# LCMeter.net
KiCad netlist of a schematic drawn in EAGLE
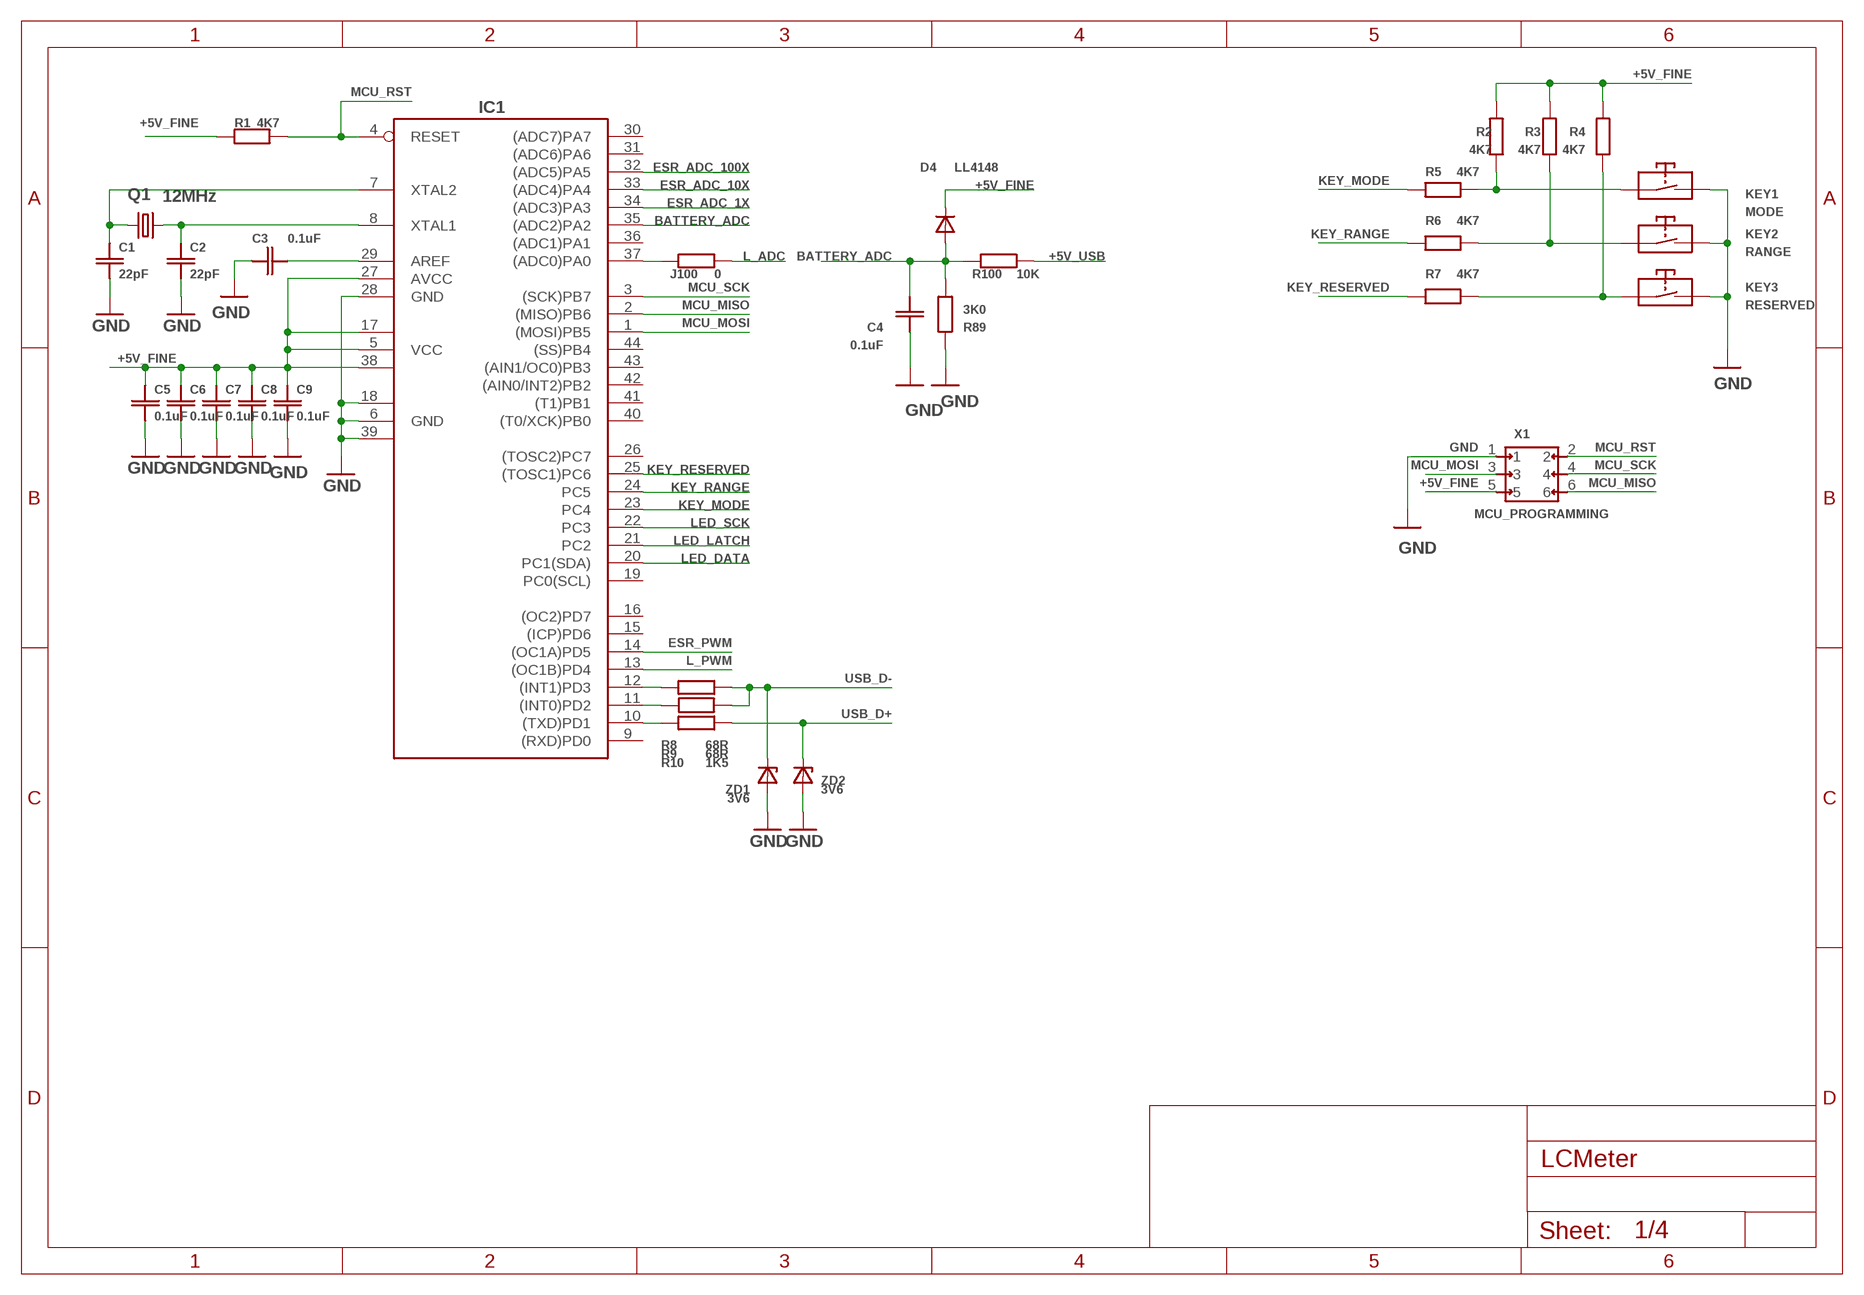
[diagram p0: schematic, sheet 1]
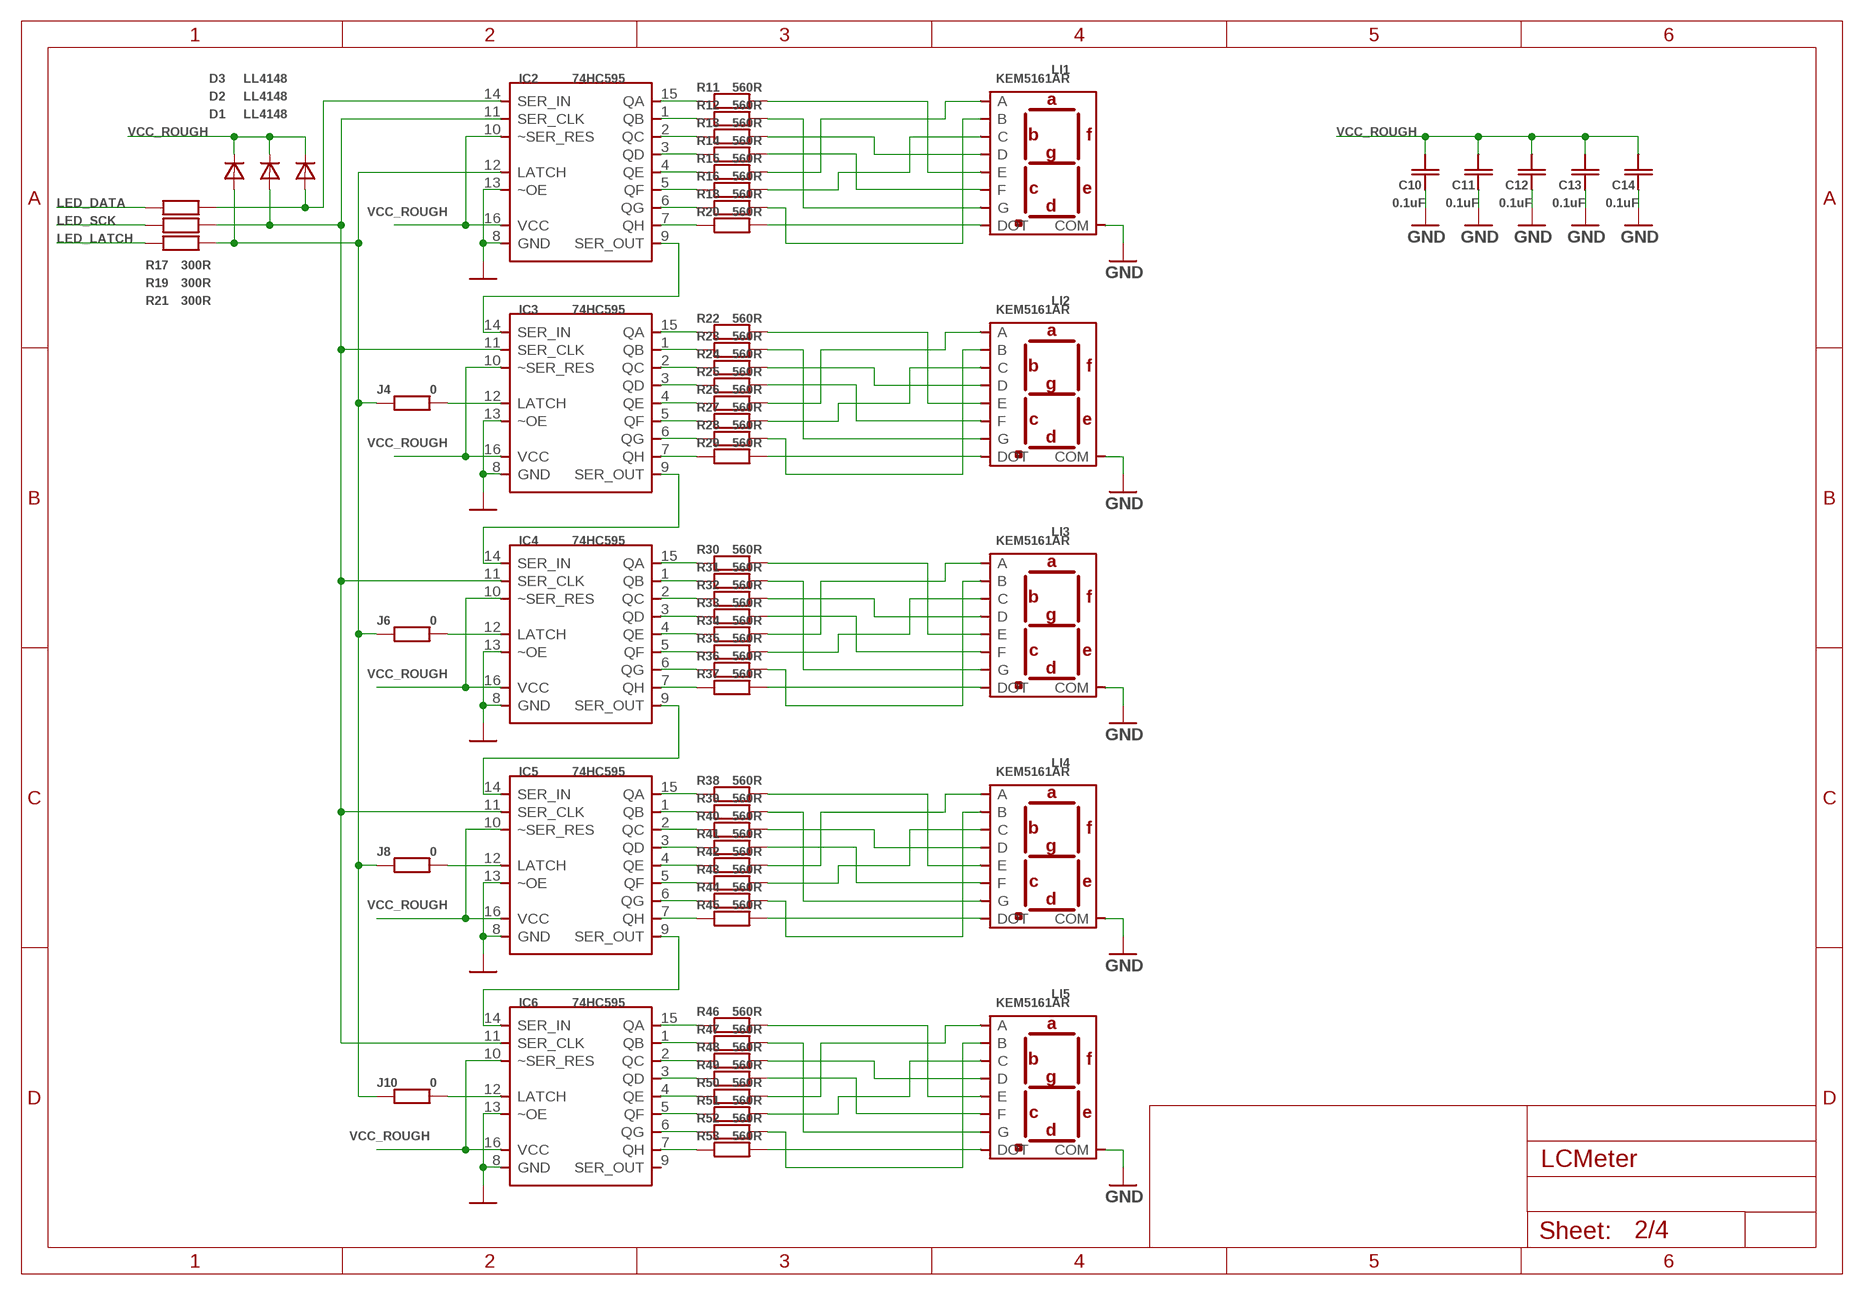
[diagram p1: schematic, sheet 2]
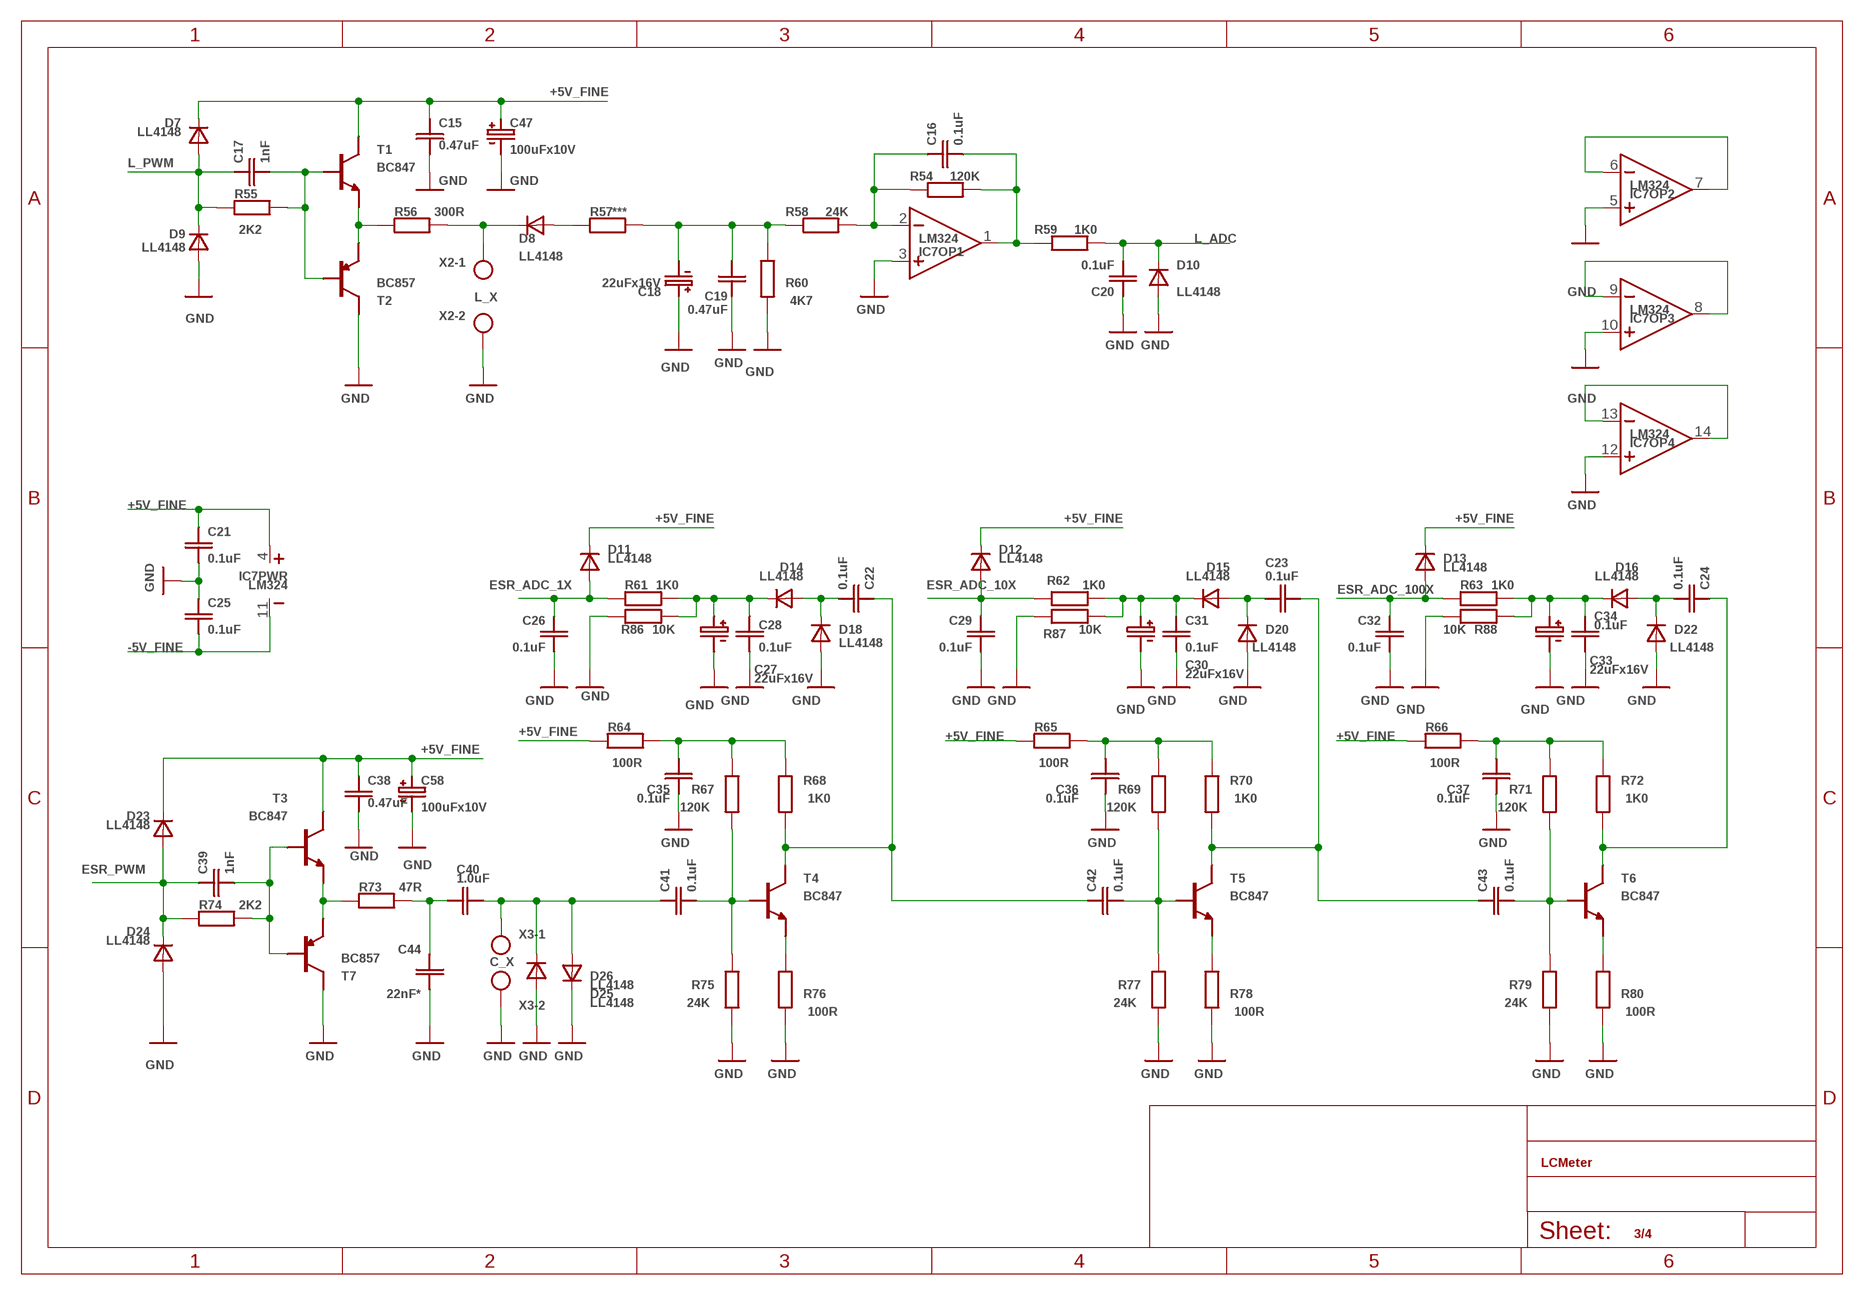
[diagram p2: schematic, sheet 3]
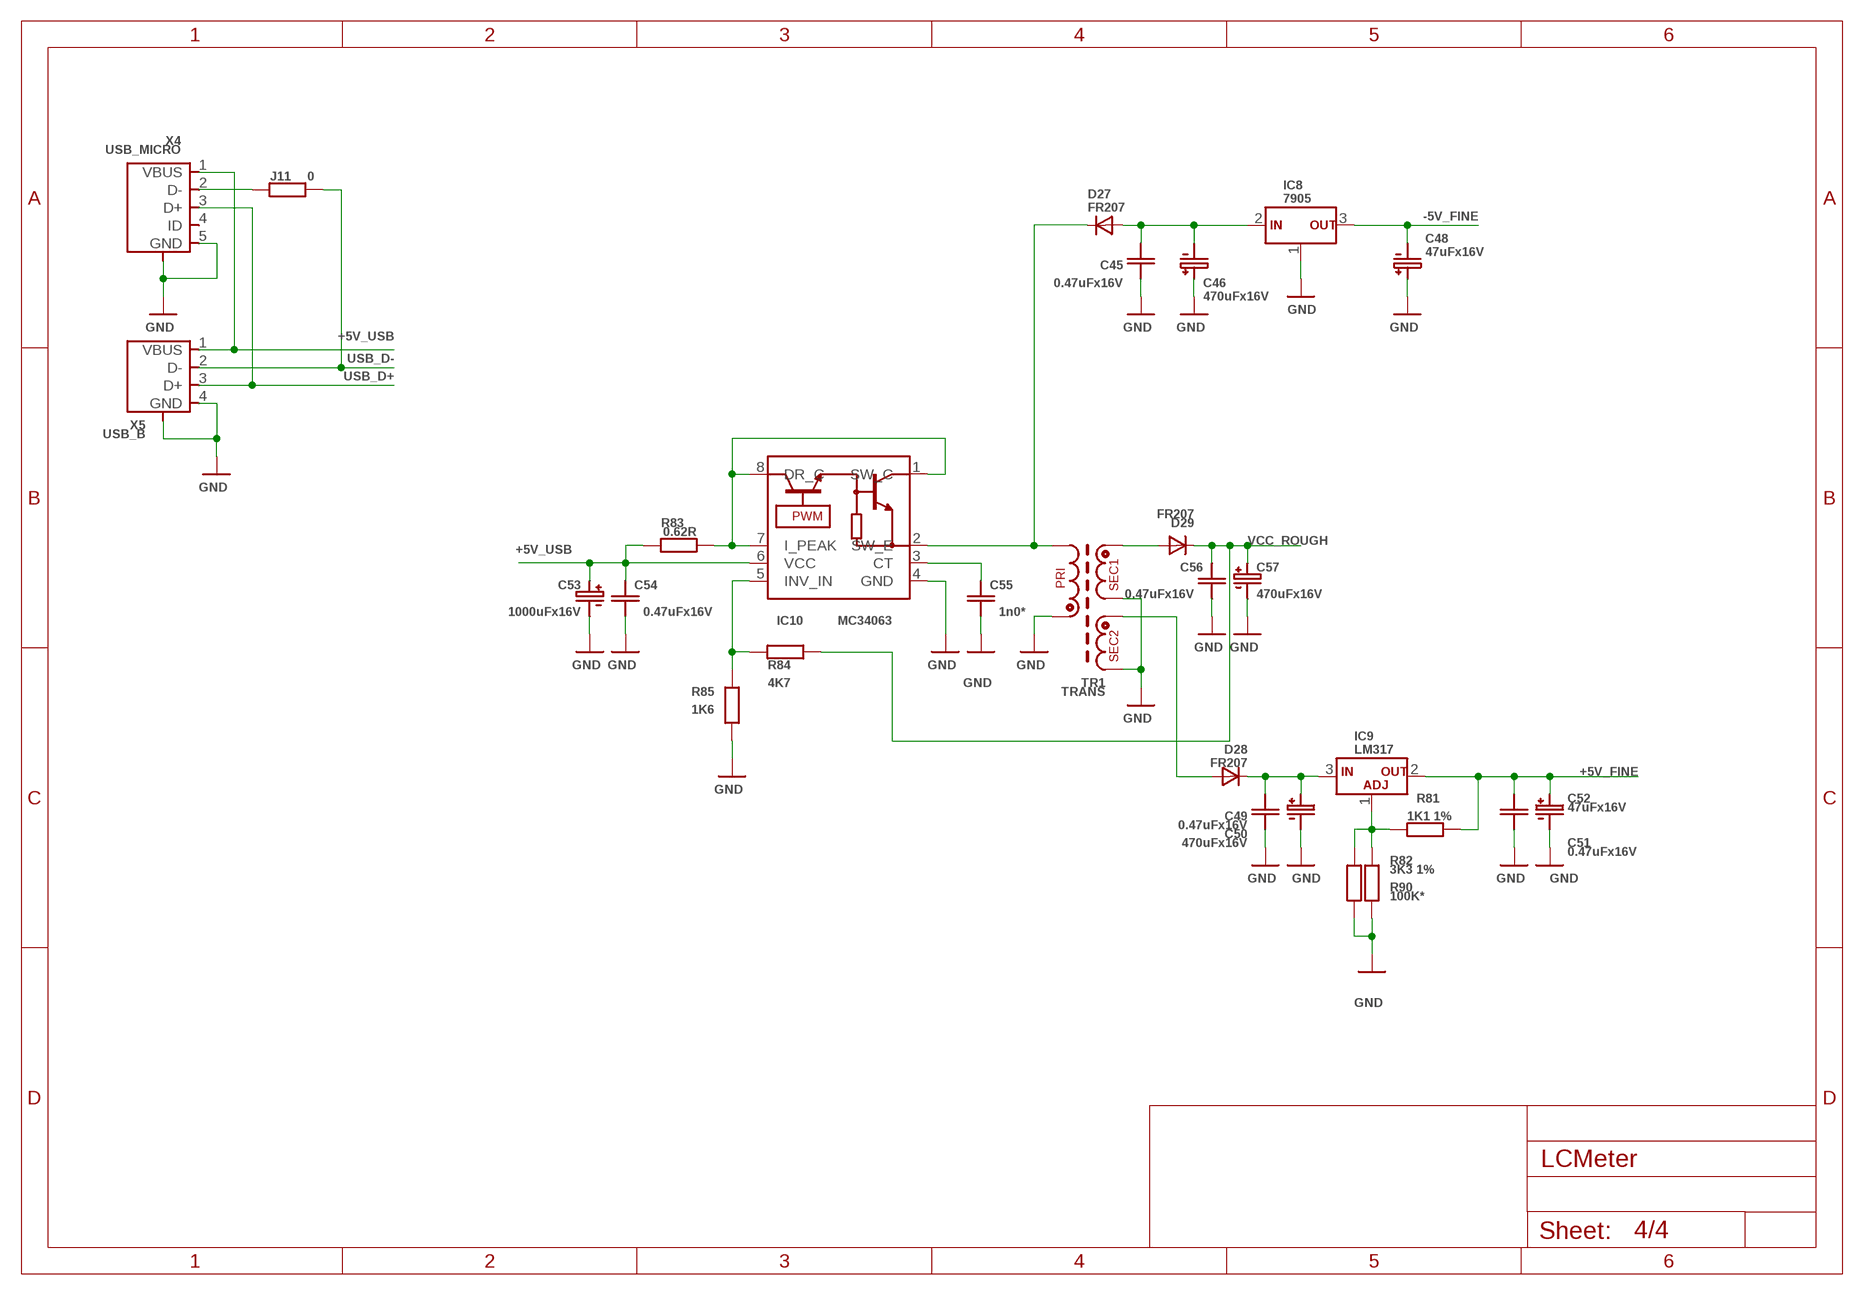
[diagram p3: schematic, sheet 4]

(export (version "E")
  (design (tool "Eeschema 10.0.6"))
  (components
    (comp (ref "C1")
      (value "22pF")
      (footprint "eagle-import:RSMD_0805")
      (libsource (lib "eagle-import") (part "CSMD_0805"))
    )
    (comp (ref "C2")
      (value "22pF")
      (footprint "eagle-import:RSMD_0805")
      (libsource (lib "eagle-import") (part "CSMD_0805"))
    )
    (comp (ref "C3")
      (value "0.1uF")
      (footprint "eagle-import:RSMD_0805")
      (libsource (lib "eagle-import") (part "CSMD_0805"))
    )
    (comp (ref "C4")
      (value "0.1uF")
      (footprint "eagle-import:RSMD_0805")
      (libsource (lib "eagle-import") (part "CSMD_0805"))
    )
    (comp (ref "C5")
      (value "0.1uF")
      (footprint "eagle-import:RSMD_0805")
      (libsource (lib "eagle-import") (part "CSMD_0805"))
    )
    (comp (ref "C6")
      (value "0.1uF")
      (footprint "eagle-import:RSMD_0805")
      (libsource (lib "eagle-import") (part "CSMD_0805"))
    )
    (comp (ref "C7")
      (value "0.1uF")
      (footprint "eagle-import:RSMD_0805")
      (libsource (lib "eagle-import") (part "CSMD_0805"))
    )
    (comp (ref "C8")
      (value "0.1uF")
      (footprint "eagle-import:RSMD_0805")
      (libsource (lib "eagle-import") (part "CSMD_0805"))
    )
    (comp (ref "C9")
      (value "0.1uF")
      (footprint "eagle-import:RSMD_0805")
      (libsource (lib "eagle-import") (part "CSMD_0805"))
    )
    (comp (ref "D4")
      (value "LL4148")
      (footprint "eagle-import:SOD-80")
      (libsource (lib "eagle-import") (part "LL4147SOD-80"))
    )
    (comp (ref "IC1")
      (value "MEGA8535")
      (footprint "eagle-import:TQFP44")
      (fields (field (name "MPN") "ATMEGA8535-16AU"))
      (libsource (lib "eagle-import") (part "MEGA8535-A"))
    )
    (comp (ref "J100")
      (value "0")
      (footprint "eagle-import:RSMD_1206_BIG_GAP")
      (libsource (lib "eagle-import") (part "RSMD_1206_BIG_GAP"))
    )
    (comp (ref "KEY1")
      (value "MODE")
      (footprint "eagle-import:KEY_7X4.5")
      (libsource (lib "eagle-import") (part "KEY(7X4.5)"))
    )
    (comp (ref "KEY2")
      (value "RANGE")
      (footprint "eagle-import:KEY_7X4.5")
      (libsource (lib "eagle-import") (part "KEY(7X4.5)"))
    )
    (comp (ref "KEY3")
      (value "RESERVED")
      (footprint "eagle-import:KEY_7X4.5")
      (libsource (lib "eagle-import") (part "KEY(7X4.5)"))
    )
    (comp (ref "Q1")
      (value "12MHz")
      (footprint "eagle-import:HC49U-V")
      (libsource (lib "eagle-import") (part "CRYSTALHC49U-V"))
    )
    (comp (ref "R1")
      (value "4K7")
      (footprint "eagle-import:RSMD_0805")
      (libsource (lib "eagle-import") (part "RSMD_0805"))
    )
    (comp (ref "R2")
      (value "4K7")
      (footprint "eagle-import:RSMD_0805")
      (libsource (lib "eagle-import") (part "RSMD_0805"))
    )
    (comp (ref "R3")
      (value "4K7")
      (footprint "eagle-import:RSMD_0805")
      (libsource (lib "eagle-import") (part "RSMD_0805"))
    )
    (comp (ref "R4")
      (value "4K7")
      (footprint "eagle-import:RSMD_0805")
      (libsource (lib "eagle-import") (part "RSMD_0805"))
    )
    (comp (ref "R5")
      (value "4K7")
      (footprint "eagle-import:RSMD_0805")
      (libsource (lib "eagle-import") (part "RSMD_0805"))
    )
    (comp (ref "R6")
      (value "4K7")
      (footprint "eagle-import:RSMD_0805")
      (libsource (lib "eagle-import") (part "RSMD_0805"))
    )
    (comp (ref "R7")
      (value "4K7")
      (footprint "eagle-import:RSMD_0805")
      (libsource (lib "eagle-import") (part "RSMD_0805"))
    )
    (comp (ref "R8")
      (value "68R")
      (footprint "eagle-import:RSMD_0805")
      (libsource (lib "eagle-import") (part "RSMD_0805"))
    )
    (comp (ref "R9")
      (value "1K5")
      (footprint "eagle-import:RSMD_0805")
      (libsource (lib "eagle-import") (part "RSMD_0805"))
    )
    (comp (ref "R10")
      (value "68R")
      (footprint "eagle-import:RSMD_0805")
      (libsource (lib "eagle-import") (part "RSMD_0805"))
    )
    (comp (ref "R89")
      (value "3K0")
      (footprint "eagle-import:RSMD_0805")
      (libsource (lib "eagle-import") (part "RSMD_0805"))
    )
    (comp (ref "R100")
      (value "10K")
      (footprint "eagle-import:RSMD_0805")
      (libsource (lib "eagle-import") (part "RSMD_0805"))
    )
    (comp (ref "X1")
      (value "MCU_PROGRAMMING")
      (footprint "eagle-import:PIN2X3_2.54MM_LOOSE_PADS")
      (libsource (lib "eagle-import") (part "PIN2X32.54MM_LOOSE_PADS"))
    )
    (comp (ref "ZD1")
      (value "3V6")
      (footprint "eagle-import:SOD-80")
      (libsource (lib "eagle-import") (part "ZENNER(SOD_80)"))
    )
    (comp (ref "ZD2")
      (value "3V6")
      (footprint "eagle-import:SOD-80")
      (libsource (lib "eagle-import") (part "ZENNER(SOD_80)"))
    )
    (comp (ref "C45")
      (value "0.47uFx16V")
      (footprint "eagle-import:RSMD_0805")
      (libsource (lib "eagle-import") (part "CSMD_0805"))
    )
    (comp (ref "C46")
      (value "470uFx16V")
      (footprint "eagle-import:CE_10MM")
      (libsource (lib "eagle-import") (part "CE10MM"))
    )
    (comp (ref "C48")
      (value "47uFx16V")
      (footprint "eagle-import:CE_6.3MM")
      (libsource (lib "eagle-import") (part "CE6.3MM"))
    )
    (comp (ref "C49")
      (value "0.47uFx16V")
      (footprint "eagle-import:RSMD_1206")
      (libsource (lib "eagle-import") (part "CSMD_1206"))
    )
    (comp (ref "C50")
      (value "470uFx16V")
      (footprint "eagle-import:CE_10MM")
      (libsource (lib "eagle-import") (part "CE10MM"))
    )
    (comp (ref "C51")
      (value "0.47uFx16V")
      (footprint "eagle-import:RSMD_0805")
      (libsource (lib "eagle-import") (part "CSMD_0805"))
    )
    (comp (ref "C52")
      (value "47uFx16V")
      (footprint "eagle-import:CE_10MM")
      (libsource (lib "eagle-import") (part "CE10MM"))
    )
    (comp (ref "C53")
      (value "1000uFx16V")
      (footprint "eagle-import:CE_10MM")
      (libsource (lib "eagle-import") (part "CE10MM"))
    )
    (comp (ref "C54")
      (value "0.47uFx16V")
      (footprint "eagle-import:RSMD_1206")
      (libsource (lib "eagle-import") (part "CSMD_1206"))
    )
    (comp (ref "C55")
      (value "1n0*")
      (footprint "eagle-import:RSMD_0805")
      (libsource (lib "eagle-import") (part "CSMD_0805"))
    )
    (comp (ref "C56")
      (value "0.47uFx16V")
      (footprint "eagle-import:RSMD_1206_BIG_GAP")
      (libsource (lib "eagle-import") (part "CSMD_1206_BIG_GAP"))
    )
    (comp (ref "C57")
      (value "470uFx16V")
      (footprint "eagle-import:CE_10MM")
      (libsource (lib "eagle-import") (part "CE10MM"))
    )
    (comp (ref "D27")
      (value "FR207")
      (footprint "eagle-import:DO-41_10MM")
      (libsource (lib "eagle-import") (part "1N4001DO-41_10MM"))
    )
    (comp (ref "D28")
      (value "FR207")
      (footprint "eagle-import:DO-41_12.5MM")
      (libsource (lib "eagle-import") (part "1N4001DO-41_12.5MM"))
    )
    (comp (ref "D29")
      (value "FR207")
      (footprint "eagle-import:DO-41_5MM")
      (libsource (lib "eagle-import") (part "1N4001DO-41_5MM"))
    )
    (comp (ref "IC8")
      (value "7905")
      (footprint "eagle-import:D2PAK")
      (libsource (lib "eagle-import") (part "7905(D2PAK)"))
    )
    (comp (ref "IC9")
      (value "LM317")
      (footprint "eagle-import:D2PAK")
      (libsource (lib "eagle-import") (part "LM317(D2PAK)"))
    )
    (comp (ref "IC10")
      (value "MC34063")
      (footprint "eagle-import:SOIC8")
      (libsource (lib "eagle-import") (part "MC34063(SO-8)"))
    )
    (comp (ref "J11")
      (value "0")
      (footprint "eagle-import:RSMD_0805")
      (libsource (lib "eagle-import") (part "RSMD_0805"))
    )
    (comp (ref "R81")
      (value "1K1 1%")
      (footprint "eagle-import:RSMD_0805")
      (libsource (lib "eagle-import") (part "RSMD_0805"))
    )
    (comp (ref "R82")
      (value "3K3 1%")
      (footprint "eagle-import:RSMD_0805")
      (libsource (lib "eagle-import") (part "RSMD_0805"))
    )
    (comp (ref "R83")
      (value "0.62R")
      (footprint "eagle-import:RSMD_1206_BIG_GAP")
      (libsource (lib "eagle-import") (part "RSMD_1206_BIG_GAP"))
    )
    (comp (ref "R84")
      (value "4K7")
      (footprint "eagle-import:R0207")
      (libsource (lib "eagle-import") (part "R0207"))
    )
    (comp (ref "R85")
      (value "1K6")
      (footprint "eagle-import:RSMD_0805")
      (libsource (lib "eagle-import") (part "RSMD_0805"))
    )
    (comp (ref "R90")
      (value "100K*")
      (footprint "eagle-import:RSMD_0805")
      (libsource (lib "eagle-import") (part "RSMD_0805"))
    )
    (comp (ref "TR1")
      (value "TRANS")
      (footprint "eagle-import:RING_25X10_3WIND_HOR")
      (libsource (lib "eagle-import") (part "TRANS_3WINDRING25X10_HOR"))
    )
    (comp (ref "X4")
      (value "USB_MICRO")
      (footprint "eagle-import:USB_MICRO_TYPE_B")
      (libsource (lib "eagle-import") (part "USB_MICROMICRO"))
    )
    (comp (ref "X5")
      (value "USB_B")
      (footprint "eagle-import:USB_TYPE_B_SMALL_PADS")
      (libsource (lib "eagle-import") (part "USB_TYPE_B(TYPE_B_SMALL_PADS)"))
    )
    (comp (ref "C10")
      (value "0.1uF")
      (footprint "eagle-import:RSMD_0805")
      (libsource (lib "eagle-import") (part "CSMD_0805"))
    )
    (comp (ref "C11")
      (value "0.1uF")
      (footprint "eagle-import:RSMD_0805")
      (libsource (lib "eagle-import") (part "CSMD_0805"))
    )
    (comp (ref "C12")
      (value "0.1uF")
      (footprint "eagle-import:RSMD_0805")
      (libsource (lib "eagle-import") (part "CSMD_0805"))
    )
    (comp (ref "C13")
      (value "0.1uF")
      (footprint "eagle-import:RSMD_0805")
      (libsource (lib "eagle-import") (part "CSMD_0805"))
    )
    (comp (ref "C14")
      (value "0.1uF")
      (footprint "eagle-import:RSMD_0805")
      (libsource (lib "eagle-import") (part "CSMD_0805"))
    )
    (comp (ref "D1")
      (value "LL4148")
      (footprint "eagle-import:SOD-80")
      (libsource (lib "eagle-import") (part "LL4147SOD-80"))
    )
    (comp (ref "D2")
      (value "LL4148")
      (footprint "eagle-import:SOD-80")
      (libsource (lib "eagle-import") (part "LL4147SOD-80"))
    )
    (comp (ref "D3")
      (value "LL4148")
      (footprint "eagle-import:SOD-80")
      (libsource (lib "eagle-import") (part "LL4147SOD-80"))
    )
    (comp (ref "IC2")
      (value "74HC595")
      (footprint "eagle-import:SOIC16")
      (libsource (lib "eagle-import") (part "74HC595(SOIC16)"))
    )
    (comp (ref "IC3")
      (value "74HC595")
      (footprint "eagle-import:SOIC16")
      (libsource (lib "eagle-import") (part "74HC595(SOIC16)"))
    )
    (comp (ref "IC4")
      (value "74HC595")
      (footprint "eagle-import:SOIC16")
      (libsource (lib "eagle-import") (part "74HC595(SOIC16)"))
    )
    (comp (ref "IC5")
      (value "74HC595")
      (footprint "eagle-import:SOIC16")
      (libsource (lib "eagle-import") (part "74HC595(SOIC16)"))
    )
    (comp (ref "IC6")
      (value "74HC595")
      (footprint "eagle-import:SOIC16")
      (libsource (lib "eagle-import") (part "74HC595(SOIC16)"))
    )
    (comp (ref "J4")
      (value "0")
      (footprint "eagle-import:RSMD_0805")
      (libsource (lib "eagle-import") (part "RSMD_0805"))
    )
    (comp (ref "J6")
      (value "0")
      (footprint "eagle-import:RSMD_0805")
      (libsource (lib "eagle-import") (part "RSMD_0805"))
    )
    (comp (ref "J8")
      (value "0")
      (footprint "eagle-import:RSMD_0805")
      (libsource (lib "eagle-import") (part "RSMD_0805"))
    )
    (comp (ref "J10")
      (value "0")
      (footprint "eagle-import:RSMD_0805")
      (libsource (lib "eagle-import") (part "RSMD_0805"))
    )
    (comp (ref "LI1")
      (value "KEM5161AR")
      (footprint "eagle-import:KEM-5161(NARROW)")
      (libsource (lib "eagle-import") (part "KEM5161(NARROW)"))
    )
    (comp (ref "LI2")
      (value "KEM5161AR")
      (footprint "eagle-import:KEM-5161(NARROW)")
      (libsource (lib "eagle-import") (part "KEM5161(NARROW)"))
    )
    (comp (ref "LI3")
      (value "KEM5161AR")
      (footprint "eagle-import:KEM-5161(NARROW)")
      (libsource (lib "eagle-import") (part "KEM5161(NARROW)"))
    )
    (comp (ref "LI4")
      (value "KEM5161AR")
      (footprint "eagle-import:KEM-5161(NARROW)")
      (libsource (lib "eagle-import") (part "KEM5161(NARROW)"))
    )
    (comp (ref "LI5")
      (value "KEM5161AR")
      (footprint "eagle-import:KEM-5161(NARROW)")
      (libsource (lib "eagle-import") (part "KEM5161(NARROW)"))
    )
    (comp (ref "R11")
      (value "560R")
      (footprint "eagle-import:RSMD_0805")
      (libsource (lib "eagle-import") (part "RSMD_0805"))
    )
    (comp (ref "R12")
      (value "560R")
      (footprint "eagle-import:RSMD_0805")
      (libsource (lib "eagle-import") (part "RSMD_0805"))
    )
    (comp (ref "R13")
      (value "560R")
      (footprint "eagle-import:RSMD_0805")
      (libsource (lib "eagle-import") (part "RSMD_0805"))
    )
    (comp (ref "R14")
      (value "560R")
      (footprint "eagle-import:RSMD_0805")
      (libsource (lib "eagle-import") (part "RSMD_0805"))
    )
    (comp (ref "R15")
      (value "560R")
      (footprint "eagle-import:RSMD_0805")
      (libsource (lib "eagle-import") (part "RSMD_0805"))
    )
    (comp (ref "R16")
      (value "560R")
      (footprint "eagle-import:RSMD_0805")
      (libsource (lib "eagle-import") (part "RSMD_0805"))
    )
    (comp (ref "R17")
      (value "300R")
      (footprint "eagle-import:RSMD_0805")
      (libsource (lib "eagle-import") (part "RSMD_0805"))
    )
    (comp (ref "R18")
      (value "560R")
      (footprint "eagle-import:RSMD_0805")
      (libsource (lib "eagle-import") (part "RSMD_0805"))
    )
    (comp (ref "R19")
      (value "300R")
      (footprint "eagle-import:RSMD_0805")
      (libsource (lib "eagle-import") (part "RSMD_0805"))
    )
    (comp (ref "R20")
      (value "560R")
      (footprint "eagle-import:RSMD_0805")
      (libsource (lib "eagle-import") (part "RSMD_0805"))
    )
    (comp (ref "R21")
      (value "300R")
      (footprint "eagle-import:RSMD_0805")
      (libsource (lib "eagle-import") (part "RSMD_0805"))
    )
    (comp (ref "R22")
      (value "560R")
      (footprint "eagle-import:RSMD_0805")
      (libsource (lib "eagle-import") (part "RSMD_0805"))
    )
    (comp (ref "R23")
      (value "560R")
      (footprint "eagle-import:RSMD_0805")
      (libsource (lib "eagle-import") (part "RSMD_0805"))
    )
    (comp (ref "R24")
      (value "560R")
      (footprint "eagle-import:RSMD_0805")
      (libsource (lib "eagle-import") (part "RSMD_0805"))
    )
    (comp (ref "R25")
      (value "560R")
      (footprint "eagle-import:RSMD_0805")
      (libsource (lib "eagle-import") (part "RSMD_0805"))
    )
    (comp (ref "R26")
      (value "560R")
      (footprint "eagle-import:RSMD_0805")
      (libsource (lib "eagle-import") (part "RSMD_0805"))
    )
    (comp (ref "R27")
      (value "560R")
      (footprint "eagle-import:RSMD_0805")
      (libsource (lib "eagle-import") (part "RSMD_0805"))
    )
    (comp (ref "R28")
      (value "560R")
      (footprint "eagle-import:RSMD_0805")
      (libsource (lib "eagle-import") (part "RSMD_0805"))
    )
    (comp (ref "R29")
      (value "560R")
      (footprint "eagle-import:RSMD_0805")
      (libsource (lib "eagle-import") (part "RSMD_0805"))
    )
    (comp (ref "R30")
      (value "560R")
      (footprint "eagle-import:RSMD_0805")
      (libsource (lib "eagle-import") (part "RSMD_0805"))
    )
    (comp (ref "R31")
      (value "560R")
      (footprint "eagle-import:RSMD_0805")
      (libsource (lib "eagle-import") (part "RSMD_0805"))
    )
    (comp (ref "R32")
      (value "560R")
      (footprint "eagle-import:RSMD_0805")
      (libsource (lib "eagle-import") (part "RSMD_0805"))
    )
    (comp (ref "R33")
      (value "560R")
      (footprint "eagle-import:RSMD_0805")
      (libsource (lib "eagle-import") (part "RSMD_0805"))
    )
    (comp (ref "R34")
      (value "560R")
      (footprint "eagle-import:RSMD_0805")
      (libsource (lib "eagle-import") (part "RSMD_0805"))
    )
    (comp (ref "R35")
      (value "560R")
      (footprint "eagle-import:RSMD_0805")
      (libsource (lib "eagle-import") (part "RSMD_0805"))
    )
    (comp (ref "R36")
      (value "560R")
      (footprint "eagle-import:RSMD_0805")
      (libsource (lib "eagle-import") (part "RSMD_0805"))
    )
    (comp (ref "R37")
      (value "560R")
      (footprint "eagle-import:RSMD_0805")
      (libsource (lib "eagle-import") (part "RSMD_0805"))
    )
    (comp (ref "R38")
      (value "560R")
      (footprint "eagle-import:RSMD_0805")
      (libsource (lib "eagle-import") (part "RSMD_0805"))
    )
    (comp (ref "R39")
      (value "560R")
      (footprint "eagle-import:RSMD_0805")
      (libsource (lib "eagle-import") (part "RSMD_0805"))
    )
    (comp (ref "R40")
      (value "560R")
      (footprint "eagle-import:RSMD_0805")
      (libsource (lib "eagle-import") (part "RSMD_0805"))
    )
    (comp (ref "R41")
      (value "560R")
      (footprint "eagle-import:RSMD_0805")
      (libsource (lib "eagle-import") (part "RSMD_0805"))
    )
    (comp (ref "R42")
      (value "560R")
      (footprint "eagle-import:RSMD_0805")
      (libsource (lib "eagle-import") (part "RSMD_0805"))
    )
    (comp (ref "R43")
      (value "560R")
      (footprint "eagle-import:RSMD_0805")
      (libsource (lib "eagle-import") (part "RSMD_0805"))
    )
    (comp (ref "R44")
      (value "560R")
      (footprint "eagle-import:RSMD_0805")
      (libsource (lib "eagle-import") (part "RSMD_0805"))
    )
    (comp (ref "R45")
      (value "560R")
      (footprint "eagle-import:RSMD_0805")
      (libsource (lib "eagle-import") (part "RSMD_0805"))
    )
    (comp (ref "R46")
      (value "560R")
      (footprint "eagle-import:RSMD_0805")
      (libsource (lib "eagle-import") (part "RSMD_0805"))
    )
    (comp (ref "R47")
      (value "560R")
      (footprint "eagle-import:RSMD_0805")
      (libsource (lib "eagle-import") (part "RSMD_0805"))
    )
    (comp (ref "R48")
      (value "560R")
      (footprint "eagle-import:RSMD_0805")
      (libsource (lib "eagle-import") (part "RSMD_0805"))
    )
    (comp (ref "R49")
      (value "560R")
      (footprint "eagle-import:RSMD_0805")
      (libsource (lib "eagle-import") (part "RSMD_0805"))
    )
    (comp (ref "R50")
      (value "560R")
      (footprint "eagle-import:RSMD_0805")
      (libsource (lib "eagle-import") (part "RSMD_0805"))
    )
    (comp (ref "R51")
      (value "560R")
      (footprint "eagle-import:RSMD_0805")
      (libsource (lib "eagle-import") (part "RSMD_0805"))
    )
    (comp (ref "R52")
      (value "560R")
      (footprint "eagle-import:RSMD_0805")
      (libsource (lib "eagle-import") (part "RSMD_0805"))
    )
    (comp (ref "R53")
      (value "560R")
      (footprint "eagle-import:RSMD_0805")
      (libsource (lib "eagle-import") (part "RSMD_0805"))
    )
    (comp (ref "C15")
      (value "0.47uF")
      (footprint "eagle-import:RSMD_0805")
      (libsource (lib "eagle-import") (part "CSMD_0805"))
    )
    (comp (ref "C16")
      (value "0.1uF")
      (footprint "eagle-import:RSMD_0805")
      (libsource (lib "eagle-import") (part "CSMD_0805"))
    )
    (comp (ref "C17")
      (value "1nF")
      (footprint "eagle-import:RSMD_0805")
      (libsource (lib "eagle-import") (part "CSMD_0805"))
    )
    (comp (ref "C18")
      (value "22uFx16V")
      (footprint "eagle-import:CE_6.3MM")
      (libsource (lib "eagle-import") (part "CE6.3MM"))
    )
    (comp (ref "C19")
      (value "0.47uF")
      (footprint "eagle-import:RSMD_1206_BIG_GAP")
      (libsource (lib "eagle-import") (part "CSMD_1206_BIG_GAP"))
    )
    (comp (ref "C20")
      (value "0.1uF")
      (footprint "eagle-import:RSMD_0805")
      (libsource (lib "eagle-import") (part "CSMD_0805"))
    )
    (comp (ref "C21")
      (value "0.1uF")
      (footprint "eagle-import:RSMD_0805")
      (libsource (lib "eagle-import") (part "CSMD_0805"))
    )
    (comp (ref "C22")
      (value "0.1uF")
      (footprint "eagle-import:RSMD_0805")
      (libsource (lib "eagle-import") (part "CSMD_0805"))
    )
    (comp (ref "C23")
      (value "0.1uF")
      (footprint "eagle-import:RSMD_0805")
      (libsource (lib "eagle-import") (part "CSMD_0805"))
    )
    (comp (ref "C24")
      (value "0.1uF")
      (footprint "eagle-import:RSMD_0805")
      (libsource (lib "eagle-import") (part "CSMD_0805"))
    )
    (comp (ref "C25")
      (value "0.1uF")
      (footprint "eagle-import:RSMD_0805")
      (libsource (lib "eagle-import") (part "CSMD_0805"))
    )
    (comp (ref "C26")
      (value "0.1uF")
      (footprint "eagle-import:RSMD_0805")
      (libsource (lib "eagle-import") (part "CSMD_0805"))
    )
    (comp (ref "C27")
      (value "22uFx16V")
      (footprint "eagle-import:CE_6.3MM")
      (libsource (lib "eagle-import") (part "CE6.3MM"))
    )
    (comp (ref "C28")
      (value "0.1uF")
      (footprint "eagle-import:RSMD_0805")
      (libsource (lib "eagle-import") (part "CSMD_0805"))
    )
    (comp (ref "C29")
      (value "0.1uF")
      (footprint "eagle-import:RSMD_0805")
      (libsource (lib "eagle-import") (part "CSMD_0805"))
    )
    (comp (ref "C30")
      (value "22uFx16V")
      (footprint "eagle-import:CE_6.3MM")
      (libsource (lib "eagle-import") (part "CE6.3MM"))
    )
    (comp (ref "C31")
      (value "0.1uF")
      (footprint "eagle-import:RSMD_0805")
      (libsource (lib "eagle-import") (part "CSMD_0805"))
    )
    (comp (ref "C32")
      (value "0.1uF")
      (footprint "eagle-import:RSMD_0805")
      (libsource (lib "eagle-import") (part "CSMD_0805"))
    )
    (comp (ref "C33")
      (value "22uFx16V")
      (footprint "eagle-import:CE_6.3MM")
      (libsource (lib "eagle-import") (part "CE6.3MM"))
    )
    (comp (ref "C34")
      (value "0.1uF")
      (footprint "eagle-import:RSMD_0805")
      (libsource (lib "eagle-import") (part "CSMD_0805"))
    )
    (comp (ref "C35")
      (value "0.1uF")
      (footprint "eagle-import:RSMD_0805")
      (libsource (lib "eagle-import") (part "CSMD_0805"))
    )
    (comp (ref "C36")
      (value "0.1uF")
      (footprint "eagle-import:RSMD_0805")
      (libsource (lib "eagle-import") (part "CSMD_0805"))
    )
    (comp (ref "C37")
      (value "0.1uF")
      (footprint "eagle-import:RSMD_0805")
      (libsource (lib "eagle-import") (part "CSMD_0805"))
    )
    (comp (ref "C38")
      (value "0.47uF")
      (footprint "eagle-import:RSMD_0805")
      (libsource (lib "eagle-import") (part "CSMD_0805"))
    )
    (comp (ref "C39")
      (value "1nF")
      (footprint "eagle-import:RSMD_0805")
      (libsource (lib "eagle-import") (part "CSMD_0805"))
    )
    (comp (ref "C40")
      (value "1.0uF")
      (footprint "eagle-import:RSMD_1206_BIG_GAP")
      (libsource (lib "eagle-import") (part "CSMD_1206_BIG_GAP"))
    )
    (comp (ref "C41")
      (value "0.1uF")
      (footprint "eagle-import:RSMD_0805")
      (libsource (lib "eagle-import") (part "CSMD_0805"))
    )
    (comp (ref "C42")
      (value "0.1uF")
      (footprint "eagle-import:RSMD_0805")
      (libsource (lib "eagle-import") (part "CSMD_0805"))
    )
    (comp (ref "C43")
      (value "0.1uF")
      (footprint "eagle-import:RSMD_0805")
      (libsource (lib "eagle-import") (part "CSMD_0805"))
    )
    (comp (ref "C44")
      (value "22nF*")
      (footprint "eagle-import:RSMD_0805")
      (libsource (lib "eagle-import") (part "CSMD_0805"))
    )
    (comp (ref "C47")
      (value "100uFx10V")
      (footprint "eagle-import:CE_6.3MM")
      (libsource (lib "eagle-import") (part "CE6.3MM"))
    )
    (comp (ref "C58")
      (value "100uFx10V")
      (footprint "eagle-import:CE_6.3MM")
      (libsource (lib "eagle-import") (part "CE6.3MM"))
    )
    (comp (ref "D7")
      (value "LL4148")
      (footprint "eagle-import:SOD-80")
      (libsource (lib "eagle-import") (part "LL4147SOD-80"))
    )
    (comp (ref "D8")
      (value "LL4148")
      (footprint "eagle-import:SOD-80")
      (libsource (lib "eagle-import") (part "LL4147SOD-80"))
    )
    (comp (ref "D9")
      (value "LL4148")
      (footprint "eagle-import:SOD-80")
      (libsource (lib "eagle-import") (part "LL4147SOD-80"))
    )
    (comp (ref "D10")
      (value "LL4148")
      (footprint "eagle-import:SOD-80")
      (libsource (lib "eagle-import") (part "LL4147SOD-80"))
    )
    (comp (ref "D11")
      (value "LL4148")
      (footprint "eagle-import:SOD-80")
      (libsource (lib "eagle-import") (part "LL4147SOD-80"))
    )
    (comp (ref "D12")
      (value "LL4148")
      (footprint "eagle-import:SOD-80")
      (libsource (lib "eagle-import") (part "LL4147SOD-80"))
    )
    (comp (ref "D13")
      (value "LL4148")
      (footprint "eagle-import:SOD-80")
      (libsource (lib "eagle-import") (part "LL4147SOD-80"))
    )
    (comp (ref "D14")
      (value "LL4148")
      (footprint "eagle-import:SOD-80")
      (libsource (lib "eagle-import") (part "LL4147SOD-80"))
    )
    (comp (ref "D15")
      (value "LL4148")
      (footprint "eagle-import:SOD-80")
      (libsource (lib "eagle-import") (part "LL4147SOD-80"))
    )
    (comp (ref "D16")
      (value "LL4148")
      (footprint "eagle-import:SOD-80")
      (libsource (lib "eagle-import") (part "LL4147SOD-80"))
    )
    (comp (ref "D18")
      (value "LL4148")
      (footprint "eagle-import:SOD-80")
      (libsource (lib "eagle-import") (part "LL4147SOD-80"))
    )
    (comp (ref "D20")
      (value "LL4148")
      (footprint "eagle-import:SOD-80")
      (libsource (lib "eagle-import") (part "LL4147SOD-80"))
    )
    (comp (ref "D22")
      (value "LL4148")
      (footprint "eagle-import:SOD-80")
      (libsource (lib "eagle-import") (part "LL4147SOD-80"))
    )
    (comp (ref "D23")
      (value "LL4148")
      (footprint "eagle-import:SOD-80")
      (libsource (lib "eagle-import") (part "LL4147SOD-80"))
    )
    (comp (ref "D24")
      (value "LL4148")
      (footprint "eagle-import:SOD-80")
      (libsource (lib "eagle-import") (part "LL4147SOD-80"))
    )
    (comp (ref "D25")
      (value "LL4148")
      (footprint "eagle-import:SOD-80")
      (libsource (lib "eagle-import") (part "LL4147SOD-80"))
    )
    (comp (ref "D26")
      (value "LL4148")
      (footprint "eagle-import:SOD-80")
      (libsource (lib "eagle-import") (part "LL4147SOD-80"))
    )
    (comp (ref "IC7")
      (value "LM324")
      (footprint "eagle-import:SOIC14")
      (libsource (lib "eagle-import") (part "LM324"))
    )
    (comp (ref "R54")
      (value "120K")
      (footprint "eagle-import:RSMD_0805")
      (libsource (lib "eagle-import") (part "RSMD_0805"))
    )
    (comp (ref "R55")
      (value "2K2")
      (footprint "eagle-import:RSMD_0805")
      (libsource (lib "eagle-import") (part "RSMD_0805"))
    )
    (comp (ref "R56")
      (value "300R")
      (footprint "eagle-import:RSMD_1206_BIG_GAP")
      (libsource (lib "eagle-import") (part "RSMD_1206_BIG_GAP"))
    )
    (comp (ref "R57")
      (value "***")
      (footprint "eagle-import:RSMD_1206_BIG_GAP")
      (libsource (lib "eagle-import") (part "RSMD_1206_BIG_GAP"))
    )
    (comp (ref "R58")
      (value "24K")
      (footprint "eagle-import:RSMD_0805")
      (libsource (lib "eagle-import") (part "RSMD_0805"))
    )
    (comp (ref "R59")
      (value "1K0")
      (footprint "eagle-import:RSMD_1206_BIG_GAP")
      (libsource (lib "eagle-import") (part "RSMD_1206_BIG_GAP"))
    )
    (comp (ref "R60")
      (value "4K7")
      (footprint "eagle-import:RSMD_0805")
      (libsource (lib "eagle-import") (part "RSMD_0805"))
    )
    (comp (ref "R61")
      (value "1K0")
      (footprint "eagle-import:RSMD_0805")
      (libsource (lib "eagle-import") (part "RSMD_0805"))
    )
    (comp (ref "R62")
      (value "1K0")
      (footprint "eagle-import:RSMD_0805")
      (libsource (lib "eagle-import") (part "RSMD_0805"))
    )
    (comp (ref "R63")
      (value "1K0")
      (footprint "eagle-import:RSMD_0805")
      (libsource (lib "eagle-import") (part "RSMD_0805"))
    )
    (comp (ref "R64")
      (value "100R")
      (footprint "eagle-import:RSMD_0805")
      (libsource (lib "eagle-import") (part "RSMD_0805"))
    )
    (comp (ref "R65")
      (value "100R")
      (footprint "eagle-import:RSMD_0805")
      (libsource (lib "eagle-import") (part "RSMD_0805"))
    )
    (comp (ref "R66")
      (value "100R")
      (footprint "eagle-import:RSMD_0805")
      (libsource (lib "eagle-import") (part "RSMD_0805"))
    )
    (comp (ref "R67")
      (value "120K")
      (footprint "eagle-import:RSMD_0805")
      (libsource (lib "eagle-import") (part "RSMD_0805"))
    )
    (comp (ref "R68")
      (value "1K0")
      (footprint "eagle-import:RSMD_0805")
      (libsource (lib "eagle-import") (part "RSMD_0805"))
    )
    (comp (ref "R69")
      (value "120K")
      (footprint "eagle-import:RSMD_0805")
      (libsource (lib "eagle-import") (part "RSMD_0805"))
    )
    (comp (ref "R70")
      (value "1K0")
      (footprint "eagle-import:RSMD_0805")
      (libsource (lib "eagle-import") (part "RSMD_0805"))
    )
    (comp (ref "R71")
      (value "120K")
      (footprint "eagle-import:RSMD_0805")
      (libsource (lib "eagle-import") (part "RSMD_0805"))
    )
    (comp (ref "R72")
      (value "1K0")
      (footprint "eagle-import:RSMD_0805")
      (libsource (lib "eagle-import") (part "RSMD_0805"))
    )
    (comp (ref "R73")
      (value "47R")
      (footprint "eagle-import:RSMD_1206_BIG_GAP")
      (libsource (lib "eagle-import") (part "RSMD_1206_BIG_GAP"))
    )
    (comp (ref "R74")
      (value "2K2")
      (footprint "eagle-import:RSMD_0805")
      (libsource (lib "eagle-import") (part "RSMD_0805"))
    )
    (comp (ref "R75")
      (value "24K")
      (footprint "eagle-import:RSMD_0805")
      (libsource (lib "eagle-import") (part "RSMD_0805"))
    )
    (comp (ref "R76")
      (value "100R")
      (footprint "eagle-import:RSMD_0805")
      (libsource (lib "eagle-import") (part "RSMD_0805"))
    )
    (comp (ref "R77")
      (value "24K")
      (footprint "eagle-import:RSMD_0805")
      (libsource (lib "eagle-import") (part "RSMD_0805"))
    )
    (comp (ref "R78")
      (value "100R")
      (footprint "eagle-import:RSMD_0805")
      (libsource (lib "eagle-import") (part "RSMD_0805"))
    )
    (comp (ref "R79")
      (value "24K")
      (footprint "eagle-import:RSMD_0805")
      (libsource (lib "eagle-import") (part "RSMD_0805"))
    )
    (comp (ref "R80")
      (value "100R")
      (footprint "eagle-import:RSMD_0805")
      (libsource (lib "eagle-import") (part "RSMD_0805"))
    )
    (comp (ref "R86")
      (value "10K")
      (footprint "eagle-import:RSMD_0805")
      (libsource (lib "eagle-import") (part "RSMD_0805"))
    )
    (comp (ref "R87")
      (value "10K")
      (footprint "eagle-import:RSMD_0805")
      (libsource (lib "eagle-import") (part "RSMD_0805"))
    )
    (comp (ref "R88")
      (value "10K")
      (footprint "eagle-import:RSMD_0805")
      (libsource (lib "eagle-import") (part "RSMD_0805"))
    )
    (comp (ref "T1")
      (value "BC847")
      (footprint "eagle-import:SOT23_SMALL_PADS")
      (libsource (lib "eagle-import") (part "BC847SOT23_SMALL_PADS"))
    )
    (comp (ref "T2")
      (value "BC857")
      (footprint "eagle-import:SOT23_SMALL_PADS")
      (libsource (lib "eagle-import") (part "BC857SOT23_SMALL_PADS"))
    )
    (comp (ref "T3")
      (value "BC847")
      (footprint "eagle-import:SOT23_SMALL_PADS")
      (libsource (lib "eagle-import") (part "BC847SOT23_SMALL_PADS"))
    )
    (comp (ref "T4")
      (value "BC847")
      (footprint "eagle-import:SOT23_SMALL_PADS")
      (libsource (lib "eagle-import") (part "BC847SOT23_SMALL_PADS"))
    )
    (comp (ref "T5")
      (value "BC847")
      (footprint "eagle-import:SOT23_SMALL_PADS")
      (libsource (lib "eagle-import") (part "BC847SOT23_SMALL_PADS"))
    )
    (comp (ref "T6")
      (value "BC847")
      (footprint "eagle-import:SOT23_SMALL_PADS")
      (libsource (lib "eagle-import") (part "BC847SOT23_SMALL_PADS"))
    )
    (comp (ref "T7")
      (value "BC857")
      (footprint "eagle-import:SOT23_SMALL_PADS")
      (libsource (lib "eagle-import") (part "BC857SOT23_SMALL_PADS"))
    )
    (comp (ref "X2")
      (value "L_X")
      (footprint "eagle-import:W237-102")
      (fields (field (name "MPN") "237-102"))
      (libsource (lib "eagle-import") (part "W237-102"))
    )
    (comp (ref "X3")
      (value "C_X")
      (footprint "eagle-import:W237-102")
      (fields (field (name "MPN") "237-102"))
      (libsource (lib "eagle-import") (part "W237-102"))
    )
  )
  (nets
    (net (code "1") (name "+5V_FINE") (class "Default")
      (node (ref "C15") (pin "PAD_0") (pinfunction "PIN0_PAD_0") (pintype "bidirectional"))
      (node (ref "C21") (pin "PAD_1") (pinfunction "PIN1_PAD_1") (pintype "bidirectional"))
      (node (ref "C38") (pin "PAD_0") (pinfunction "PIN0_PAD_0") (pintype "bidirectional"))
      (node (ref "C47") (pin "+") (pinfunction "+_+") (pintype "bidirectional"))
      (node (ref "C5") (pin "PAD_1") (pinfunction "PIN1_PAD_1") (pintype "bidirectional"))
      (node (ref "C51") (pin "PAD_1") (pinfunction "PIN1_PAD_1") (pintype "bidirectional"))
      (node (ref "C52") (pin "+") (pinfunction "+_+") (pintype "bidirectional"))
      (node (ref "C58") (pin "+") (pinfunction "+_+") (pintype "bidirectional"))
      (node (ref "C6") (pin "PAD_1") (pinfunction "PIN1_PAD_1") (pintype "bidirectional"))
      (node (ref "C7") (pin "PAD_1") (pinfunction "PIN1_PAD_1") (pintype "bidirectional"))
      (node (ref "C8") (pin "PAD_1") (pinfunction "PIN1_PAD_1") (pintype "bidirectional"))
      (node (ref "C9") (pin "PAD_1") (pinfunction "PIN1_PAD_1") (pintype "bidirectional"))
      (node (ref "D11") (pin "CATHODE") (pinfunction "CATHODE_CATHODE") (pintype "passive"))
      (node (ref "D12") (pin "CATHODE") (pinfunction "CATHODE_CATHODE") (pintype "passive"))
      (node (ref "D13") (pin "CATHODE") (pinfunction "CATHODE_CATHODE") (pintype "passive"))
      (node (ref "D23") (pin "CATHODE") (pinfunction "CATHODE_CATHODE") (pintype "passive"))
      (node (ref "D4") (pin "CATHODE") (pinfunction "CATHODE_CATHODE") (pintype "passive"))
      (node (ref "D7") (pin "CATHODE") (pinfunction "CATHODE_CATHODE") (pintype "passive"))
      (node (ref "IC1") (pin "17") (pinfunction "VCC1_17") (pintype "power_in"))
      (node (ref "IC1") (pin "27") (pinfunction "AVCC_27") (pintype "power_in"))
      (node (ref "IC1") (pin "38") (pinfunction "VCC2_38") (pintype "power_in"))
      (node (ref "IC1") (pin "5") (pinfunction "VCC_5") (pintype "power_in"))
      (node (ref "IC7") (pin "4") (pinfunction "VCC_4") (pintype "power_in"))
      (node (ref "IC9") (pin "2") (pinfunction "OUT_2") (pintype "output"))
      (node (ref "R1") (pin "PAD_0") (pinfunction "PIN0_PAD_0") (pintype "passive"))
      (node (ref "R2") (pin "PAD_1") (pinfunction "PIN1_PAD_1") (pintype "passive"))
      (node (ref "R3") (pin "PAD_1") (pinfunction "PIN1_PAD_1") (pintype "passive"))
      (node (ref "R4") (pin "PAD_1") (pinfunction "PIN1_PAD_1") (pintype "passive"))
      (node (ref "R64") (pin "PAD_0") (pinfunction "PIN0_PAD_0") (pintype "passive"))
      (node (ref "R65") (pin "PAD_0") (pinfunction "PIN0_PAD_0") (pintype "passive"))
      (node (ref "R66") (pin "PAD_0") (pinfunction "PIN0_PAD_0") (pintype "passive"))
      (node (ref "R81") (pin "PAD_0") (pinfunction "PIN0_PAD_0") (pintype "passive"))
      (node (ref "T1") (pin "3") (pinfunction "C_3") (pintype "bidirectional"))
      (node (ref "T3") (pin "3") (pinfunction "C_3") (pintype "bidirectional"))
      (node (ref "X1") (pin "5") (pinfunction "5_5") (pintype "bidirectional"))
    )
    (net (code "2") (name "+5V_USB") (class "Default")
      (node (ref "C53") (pin "+") (pinfunction "+_+") (pintype "bidirectional"))
      (node (ref "C54") (pin "PAD_1") (pinfunction "PIN1_PAD_1") (pintype "bidirectional"))
      (node (ref "IC10") (pin "6") (pinfunction "VCC_6") (pintype "bidirectional"))
      (node (ref "R100") (pin "PAD_0") (pinfunction "PIN0_PAD_0") (pintype "passive"))
      (node (ref "R83") (pin "PAD_0") (pinfunction "PIN0_PAD_0") (pintype "passive"))
      (node (ref "X4") (pin "1") (pinfunction "VBUS_1") (pintype "bidirectional"))
      (node (ref "X5") (pin "1") (pinfunction "VBUS_1") (pintype "bidirectional"))
    )
    (net (code "3") (name "-5V_FINE") (class "Default")
      (node (ref "C25") (pin "PAD_0") (pinfunction "PIN0_PAD_0") (pintype "bidirectional"))
      (node (ref "C48") (pin "-") (pinfunction "-_-") (pintype "bidirectional"))
      (node (ref "IC7") (pin "11") (pinfunction "GND_11") (pintype "power_in"))
      (node (ref "IC8") (pin "3") (pinfunction "OUT_3") (pintype "output"))
    )
    (net (code "4") (name "BATTERY_ADC") (class "Default")
      (node (ref "C4") (pin "PAD_1") (pinfunction "PIN1_PAD_1") (pintype "bidirectional"))
      (node (ref "D4") (pin "ANODE") (pinfunction "ANODE_ANODE") (pintype "passive"))
      (node (ref "IC1") (pin "35") (pinfunction "(ADC2)PA2_35") (pintype "bidirectional"))
      (node (ref "R100") (pin "PAD_1") (pinfunction "PIN1_PAD_1") (pintype "passive"))
      (node (ref "R89") (pin "PAD_0") (pinfunction "PIN0_PAD_0") (pintype "passive"))
    )
    (net (code "5") (name "ESR_ADC_1X") (class "Default")
      (node (ref "C26") (pin "PAD_1") (pinfunction "PIN1_PAD_1") (pintype "bidirectional"))
      (node (ref "D11") (pin "ANODE") (pinfunction "ANODE_ANODE") (pintype "passive"))
      (node (ref "IC1") (pin "34") (pinfunction "(ADC3)PA3_34") (pintype "bidirectional"))
      (node (ref "R61") (pin "PAD_1") (pinfunction "PIN1_PAD_1") (pintype "passive"))
    )
    (net (code "6") (name "ESR_ADC_10X") (class "Default")
      (node (ref "C29") (pin "PAD_1") (pinfunction "PIN1_PAD_1") (pintype "bidirectional"))
      (node (ref "D12") (pin "ANODE") (pinfunction "ANODE_ANODE") (pintype "passive"))
      (node (ref "IC1") (pin "33") (pinfunction "(ADC4)PA4_33") (pintype "bidirectional"))
      (node (ref "R62") (pin "PAD_1") (pinfunction "PIN1_PAD_1") (pintype "passive"))
    )
    (net (code "7") (name "ESR_ADC_100X") (class "Default")
      (node (ref "C32") (pin "PAD_1") (pinfunction "PIN1_PAD_1") (pintype "bidirectional"))
      (node (ref "D13") (pin "ANODE") (pinfunction "ANODE_ANODE") (pintype "passive"))
      (node (ref "IC1") (pin "32") (pinfunction "(ADC5)PA5_32") (pintype "bidirectional"))
      (node (ref "R63") (pin "PAD_1") (pinfunction "PIN1_PAD_1") (pintype "passive"))
    )
    (net (code "8") (name "ESR_PWM") (class "Default")
      (node (ref "C39") (pin "PAD_1") (pinfunction "PIN1_PAD_1") (pintype "bidirectional"))
      (node (ref "D23") (pin "ANODE") (pinfunction "ANODE_ANODE") (pintype "passive"))
      (node (ref "D24") (pin "CATHODE") (pinfunction "CATHODE_CATHODE") (pintype "passive"))
      (node (ref "IC1") (pin "14") (pinfunction "(OC1A)PD5_14") (pintype "bidirectional"))
      (node (ref "R74") (pin "PAD_0") (pinfunction "PIN0_PAD_0") (pintype "passive"))
    )
    (net (code "9") (name "GND") (class "Default")
      (node (ref "C1") (pin "PAD_0") (pinfunction "PIN0_PAD_0") (pintype "bidirectional"))
      (node (ref "C10") (pin "PAD_0") (pinfunction "PIN0_PAD_0") (pintype "bidirectional"))
      (node (ref "C11") (pin "PAD_0") (pinfunction "PIN0_PAD_0") (pintype "bidirectional"))
      (node (ref "C12") (pin "PAD_0") (pinfunction "PIN0_PAD_0") (pintype "bidirectional"))
      (node (ref "C13") (pin "PAD_0") (pinfunction "PIN0_PAD_0") (pintype "bidirectional"))
      (node (ref "C14") (pin "PAD_0") (pinfunction "PIN0_PAD_0") (pintype "bidirectional"))
      (node (ref "C15") (pin "PAD_1") (pinfunction "PIN1_PAD_1") (pintype "bidirectional"))
      (node (ref "C18") (pin "+") (pinfunction "+_+") (pintype "bidirectional"))
      (node (ref "C19") (pin "PAD_0") (pinfunction "PIN0_PAD_0") (pintype "bidirectional"))
      (node (ref "C2") (pin "PAD_0") (pinfunction "PIN0_PAD_0") (pintype "bidirectional"))
      (node (ref "C20") (pin "PAD_1") (pinfunction "PIN1_PAD_1") (pintype "bidirectional"))
      (node (ref "C21") (pin "PAD_0") (pinfunction "PIN0_PAD_0") (pintype "bidirectional"))
      (node (ref "C25") (pin "PAD_1") (pinfunction "PIN1_PAD_1") (pintype "bidirectional"))
      (node (ref "C26") (pin "PAD_0") (pinfunction "PIN0_PAD_0") (pintype "bidirectional"))
      (node (ref "C27") (pin "-") (pinfunction "-_-") (pintype "bidirectional"))
      (node (ref "C28") (pin "PAD_0") (pinfunction "PIN0_PAD_0") (pintype "bidirectional"))
      (node (ref "C29") (pin "PAD_0") (pinfunction "PIN0_PAD_0") (pintype "bidirectional"))
      (node (ref "C3") (pin "PAD_0") (pinfunction "PIN0_PAD_0") (pintype "bidirectional"))
      (node (ref "C30") (pin "-") (pinfunction "-_-") (pintype "bidirectional"))
      (node (ref "C31") (pin "PAD_0") (pinfunction "PIN0_PAD_0") (pintype "bidirectional"))
      (node (ref "C32") (pin "PAD_0") (pinfunction "PIN0_PAD_0") (pintype "bidirectional"))
      (node (ref "C33") (pin "-") (pinfunction "-_-") (pintype "bidirectional"))
      (node (ref "C34") (pin "PAD_0") (pinfunction "PIN0_PAD_0") (pintype "bidirectional"))
      (node (ref "C35") (pin "PAD_1") (pinfunction "PIN1_PAD_1") (pintype "bidirectional"))
      (node (ref "C36") (pin "PAD_1") (pinfunction "PIN1_PAD_1") (pintype "bidirectional"))
      (node (ref "C37") (pin "PAD_1") (pinfunction "PIN1_PAD_1") (pintype "bidirectional"))
      (node (ref "C38") (pin "PAD_1") (pinfunction "PIN1_PAD_1") (pintype "bidirectional"))
      (node (ref "C4") (pin "PAD_0") (pinfunction "PIN0_PAD_0") (pintype "bidirectional"))
      (node (ref "C44") (pin "PAD_0") (pinfunction "PIN0_PAD_0") (pintype "bidirectional"))
      (node (ref "C45") (pin "PAD_0") (pinfunction "PIN0_PAD_0") (pintype "bidirectional"))
      (node (ref "C46") (pin "+") (pinfunction "+_+") (pintype "bidirectional"))
      (node (ref "C47") (pin "-") (pinfunction "-_-") (pintype "bidirectional"))
      (node (ref "C48") (pin "+") (pinfunction "+_+") (pintype "bidirectional"))
      (node (ref "C49") (pin "PAD_0") (pinfunction "PIN0_PAD_0") (pintype "bidirectional"))
      (node (ref "C5") (pin "PAD_0") (pinfunction "PIN0_PAD_0") (pintype "bidirectional"))
      (node (ref "C50") (pin "-") (pinfunction "-_-") (pintype "bidirectional"))
      (node (ref "C51") (pin "PAD_0") (pinfunction "PIN0_PAD_0") (pintype "bidirectional"))
      (node (ref "C52") (pin "-") (pinfunction "-_-") (pintype "bidirectional"))
      (node (ref "C53") (pin "-") (pinfunction "-_-") (pintype "bidirectional"))
      (node (ref "C54") (pin "PAD_0") (pinfunction "PIN0_PAD_0") (pintype "bidirectional"))
      (node (ref "C55") (pin "PAD_0") (pinfunction "PIN0_PAD_0") (pintype "bidirectional"))
      (node (ref "C56") (pin "PAD_0") (pinfunction "PIN0_PAD_0") (pintype "bidirectional"))
      (node (ref "C57") (pin "-") (pinfunction "-_-") (pintype "bidirectional"))
      (node (ref "C58") (pin "-") (pinfunction "-_-") (pintype "bidirectional"))
      (node (ref "C6") (pin "PAD_0") (pinfunction "PIN0_PAD_0") (pintype "bidirectional"))
      (node (ref "C7") (pin "PAD_0") (pinfunction "PIN0_PAD_0") (pintype "bidirectional"))
      (node (ref "C8") (pin "PAD_0") (pinfunction "PIN0_PAD_0") (pintype "bidirectional"))
      (node (ref "C9") (pin "PAD_0") (pinfunction "PIN0_PAD_0") (pintype "bidirectional"))
      (node (ref "D10") (pin "ANODE") (pinfunction "ANODE_ANODE") (pintype "passive"))
      (node (ref "D18") (pin "ANODE") (pinfunction "ANODE_ANODE") (pintype "passive"))
      (node (ref "D20") (pin "ANODE") (pinfunction "ANODE_ANODE") (pintype "passive"))
      (node (ref "D22") (pin "ANODE") (pinfunction "ANODE_ANODE") (pintype "passive"))
      (node (ref "D24") (pin "ANODE") (pinfunction "ANODE_ANODE") (pintype "passive"))
      (node (ref "D25") (pin "ANODE") (pinfunction "ANODE_ANODE") (pintype "passive"))
      (node (ref "D26") (pin "CATHODE") (pinfunction "CATHODE_CATHODE") (pintype "passive"))
      (node (ref "D9") (pin "ANODE") (pinfunction "ANODE_ANODE") (pintype "passive"))
      (node (ref "IC1") (pin "18") (pinfunction "GND1_18") (pintype "power_in"))
      (node (ref "IC1") (pin "28") (pinfunction "GND_28") (pintype "power_in"))
      (node (ref "IC1") (pin "39") (pinfunction "GND2_39") (pintype "power_in"))
      (node (ref "IC1") (pin "6") (pinfunction "GND_6") (pintype "power_in"))
      (node (ref "IC10") (pin "4") (pinfunction "GND_4") (pintype "bidirectional"))
      (node (ref "IC2") (pin "13") (pinfunction "~{OE}_13") (pintype "bidirectional"))
      (node (ref "IC2") (pin "8") (pinfunction "GND_8") (pintype "bidirectional"))
      (node (ref "IC3") (pin "13") (pinfunction "~{OE}_13") (pintype "bidirectional"))
      (node (ref "IC3") (pin "8") (pinfunction "GND_8") (pintype "bidirectional"))
      (node (ref "IC4") (pin "13") (pinfunction "~{OE}_13") (pintype "bidirectional"))
      (node (ref "IC4") (pin "8") (pinfunction "GND_8") (pintype "bidirectional"))
      (node (ref "IC5") (pin "13") (pinfunction "~{OE}_13") (pintype "bidirectional"))
      (node (ref "IC5") (pin "8") (pinfunction "GND_8") (pintype "bidirectional"))
      (node (ref "IC6") (pin "13") (pinfunction "~{OE}_13") (pintype "bidirectional"))
      (node (ref "IC6") (pin "8") (pinfunction "GND_8") (pintype "bidirectional"))
      (node (ref "IC7") (pin "10") (pinfunction "IN+_10") (pintype "input"))
      (node (ref "IC7") (pin "12") (pinfunction "IN+_12") (pintype "input"))
      (node (ref "IC7") (pin "3") (pinfunction "IN+_3") (pintype "input"))
      (node (ref "IC7") (pin "5") (pinfunction "IN+_5") (pintype "input"))
      (node (ref "IC8") (pin "1") (pinfunction "GND_1") (pintype "input"))
      (node (ref "KEY1") (pin "3") (pinfunction "2_3") (pintype "bidirectional"))
      (node (ref "KEY1") (pin "4") (pinfunction "2_4") (pintype "bidirectional"))
      (node (ref "KEY2") (pin "3") (pinfunction "2_3") (pintype "bidirectional"))
      (node (ref "KEY2") (pin "4") (pinfunction "2_4") (pintype "bidirectional"))
      (node (ref "KEY3") (pin "3") (pinfunction "2_3") (pintype "bidirectional"))
      (node (ref "KEY3") (pin "4") (pinfunction "2_4") (pintype "bidirectional"))
      (node (ref "LI1") (pin "3") (pinfunction "COM_3") (pintype "passive"))
      (node (ref "LI1") (pin "8") (pinfunction "COM_8") (pintype "passive"))
      (node (ref "LI2") (pin "3") (pinfunction "COM_3") (pintype "passive"))
      (node (ref "LI2") (pin "8") (pinfunction "COM_8") (pintype "passive"))
      (node (ref "LI3") (pin "3") (pinfunction "COM_3") (pintype "passive"))
      (node (ref "LI3") (pin "8") (pinfunction "COM_8") (pintype "passive"))
      (node (ref "LI4") (pin "3") (pinfunction "COM_3") (pintype "passive"))
      (node (ref "LI4") (pin "8") (pinfunction "COM_8") (pintype "passive"))
      (node (ref "LI5") (pin "3") (pinfunction "COM_3") (pintype "passive"))
      (node (ref "LI5") (pin "8") (pinfunction "COM_8") (pintype "passive"))
      (node (ref "R60") (pin "PAD_1") (pinfunction "PIN1_PAD_1") (pintype "passive"))
      (node (ref "R75") (pin "PAD_0") (pinfunction "PIN0_PAD_0") (pintype "passive"))
      (node (ref "R76") (pin "PAD_0") (pinfunction "PIN0_PAD_0") (pintype "passive"))
      (node (ref "R77") (pin "PAD_0") (pinfunction "PIN0_PAD_0") (pintype "passive"))
      (node (ref "R78") (pin "PAD_0") (pinfunction "PIN0_PAD_0") (pintype "passive"))
      (node (ref "R79") (pin "PAD_0") (pinfunction "PIN0_PAD_0") (pintype "passive"))
      (node (ref "R80") (pin "PAD_0") (pinfunction "PIN0_PAD_0") (pintype "passive"))
      (node (ref "R82") (pin "PAD_0") (pinfunction "PIN0_PAD_0") (pintype "passive"))
      (node (ref "R85") (pin "PAD_0") (pinfunction "PIN0_PAD_0") (pintype "passive"))
      (node (ref "R86") (pin "PAD_0") (pinfunction "PIN0_PAD_0") (pintype "passive"))
      (node (ref "R87") (pin "PAD_0") (pinfunction "PIN0_PAD_0") (pintype "passive"))
      (node (ref "R88") (pin "PAD_0") (pinfunction "PIN0_PAD_0") (pintype "passive"))
      (node (ref "R89") (pin "PAD_1") (pinfunction "PIN1_PAD_1") (pintype "passive"))
      (node (ref "R90") (pin "PAD_0") (pinfunction "PIN0_PAD_0") (pintype "passive"))
      (node (ref "T2") (pin "3") (pinfunction "C_3") (pintype "bidirectional"))
      (node (ref "T7") (pin "3") (pinfunction "C_3") (pintype "bidirectional"))
      (node (ref "TR1") (pin "W1_START") (pinfunction "PRI_START_W1_START") (pintype "bidirectional"))
      (node (ref "TR1") (pin "W2_END") (pinfunction "SEC1_END_W2_END") (pintype "bidirectional"))
      (node (ref "TR1") (pin "W3_END") (pinfunction "SEC2_END_W3_END") (pintype "bidirectional"))
      (node (ref "X1") (pin "1") (pinfunction "1_1") (pintype "bidirectional"))
      (node (ref "X2") (pin "2") (pinfunction "KL_2") (pintype "passive"))
      (node (ref "X3") (pin "2") (pinfunction "KL_2") (pintype "passive"))
      (node (ref "X4") (pin "5") (pinfunction "GND_5") (pintype "bidirectional"))
      (node (ref "X4") (pin "PACKAGE1") (pinfunction "PACKAGE_PACKAGE1") (pintype "bidirectional"))
      (node (ref "X4") (pin "PACKAGE2") (pinfunction "PACKAGE_PACKAGE2") (pintype "bidirectional"))
      (node (ref "X4") (pin "PACKAGE3") (pinfunction "PACKAGE_PACKAGE3") (pintype "bidirectional"))
      (node (ref "X4") (pin "PACKAGE4") (pinfunction "PACKAGE_PACKAGE4") (pintype "bidirectional"))
      (node (ref "X4") (pin "PACKAGE5") (pinfunction "PACKAGE_PACKAGE5") (pintype "bidirectional"))
      (node (ref "X5") (pin "4") (pinfunction "GND_4") (pintype "bidirectional"))
      (node (ref "X5") (pin "PACKAGE_PAD1") (pinfunction "PACKAGE_PACKAGE_PAD1") (pintype "bidirectional"))
      (node (ref "X5") (pin "PACKAGE_PAD2") (pinfunction "PACKAGE_PACKAGE_PAD2") (pintype "bidirectional"))
      (node (ref "ZD1") (pin "ANODE") (pinfunction "ANODE_ANODE") (pintype "passive"))
      (node (ref "ZD2") (pin "ANODE") (pinfunction "ANODE_ANODE") (pintype "passive"))
    )
    (net (code "10") (name "KEY_MODE") (class "Default")
      (node (ref "IC1") (pin "23") (pinfunction "PC4_23") (pintype "bidirectional"))
      (node (ref "R5") (pin "PAD_1") (pinfunction "PIN1_PAD_1") (pintype "passive"))
    )
    (net (code "11") (name "KEY_RANGE") (class "Default")
      (node (ref "IC1") (pin "24") (pinfunction "PC5_24") (pintype "bidirectional"))
      (node (ref "R6") (pin "PAD_1") (pinfunction "PIN1_PAD_1") (pintype "passive"))
    )
    (net (code "12") (name "KEY_RESERVED") (class "Default")
      (node (ref "IC1") (pin "25") (pinfunction "(TOSC1)PC6_25") (pintype "bidirectional"))
      (node (ref "R7") (pin "PAD_1") (pinfunction "PIN1_PAD_1") (pintype "passive"))
    )
    (net (code "13") (name "LED_DATA") (class "Default")
      (node (ref "IC1") (pin "20") (pinfunction "PC1(SDA)_20") (pintype "bidirectional"))
      (node (ref "R17") (pin "PAD_0") (pinfunction "PIN0_PAD_0") (pintype "passive"))
    )
    (net (code "14") (name "LED_LATCH") (class "Default")
      (node (ref "IC1") (pin "21") (pinfunction "PC2_21") (pintype "bidirectional"))
      (node (ref "R21") (pin "PAD_0") (pinfunction "PIN0_PAD_0") (pintype "passive"))
    )
    (net (code "15") (name "LED_SCK") (class "Default")
      (node (ref "IC1") (pin "22") (pinfunction "PC3_22") (pintype "bidirectional"))
      (node (ref "R19") (pin "PAD_0") (pinfunction "PIN0_PAD_0") (pintype "passive"))
    )
    (net (code "16") (name "L_ADC") (class "Default")
      (node (ref "C20") (pin "PAD_0") (pinfunction "PIN0_PAD_0") (pintype "bidirectional"))
      (node (ref "D10") (pin "CATHODE") (pinfunction "CATHODE_CATHODE") (pintype "passive"))
      (node (ref "J100") (pin "PAD_0") (pinfunction "PIN0_PAD_0") (pintype "passive"))
      (node (ref "R59") (pin "PAD_1") (pinfunction "PIN1_PAD_1") (pintype "passive"))
    )
    (net (code "17") (name "L_PWM") (class "Default")
      (node (ref "C17") (pin "PAD_1") (pinfunction "PIN1_PAD_1") (pintype "bidirectional"))
      (node (ref "D7") (pin "ANODE") (pinfunction "ANODE_ANODE") (pintype "passive"))
      (node (ref "D9") (pin "CATHODE") (pinfunction "CATHODE_CATHODE") (pintype "passive"))
      (node (ref "IC1") (pin "13") (pinfunction "(OC1B)PD4_13") (pintype "bidirectional"))
      (node (ref "R55") (pin "PAD_0") (pinfunction "PIN0_PAD_0") (pintype "passive"))
    )
    (net (code "18") (name "MCU_MISO") (class "Default")
      (node (ref "IC1") (pin "2") (pinfunction "(MISO)PB6_2") (pintype "bidirectional"))
      (node (ref "X1") (pin "6") (pinfunction "6_6") (pintype "bidirectional"))
    )
    (net (code "19") (name "MCU_MOSI") (class "Default")
      (node (ref "IC1") (pin "1") (pinfunction "(MOSI)PB5_1") (pintype "bidirectional"))
      (node (ref "X1") (pin "3") (pinfunction "3_3") (pintype "bidirectional"))
    )
    (net (code "20") (name "MCU_RST") (class "Default")
      (node (ref "IC1") (pin "4") (pinfunction "RESET_4") (pintype "input"))
      (node (ref "R1") (pin "PAD_1") (pinfunction "PIN1_PAD_1") (pintype "passive"))
      (node (ref "X1") (pin "2") (pinfunction "2_2") (pintype "bidirectional"))
    )
    (net (code "21") (name "MCU_SCK") (class "Default")
      (node (ref "IC1") (pin "3") (pinfunction "(SCK)PB7_3") (pintype "bidirectional"))
      (node (ref "X1") (pin "4") (pinfunction "4_4") (pintype "bidirectional"))
    )
    (net (code "22") (name "Net-(C1-PIN1)") (class "Default")
      (node (ref "C1") (pin "PAD_1") (pinfunction "PIN1_PAD_1") (pintype "bidirectional"))
      (node (ref "IC1") (pin "7") (pinfunction "XTAL2_7") (pintype "bidirectional"))
      (node (ref "Q1") (pin "1") (pinfunction "1_1") (pintype "passive"))
    )
    (net (code "23") (name "Net-(C2-PIN1)") (class "Default")
      (node (ref "C2") (pin "PAD_1") (pinfunction "PIN1_PAD_1") (pintype "bidirectional"))
      (node (ref "IC1") (pin "8") (pinfunction "XTAL1_8") (pintype "bidirectional"))
      (node (ref "Q1") (pin "2") (pinfunction "2_2") (pintype "passive"))
    )
    (net (code "24") (name "Net-(C3-PIN1)") (class "Default")
      (node (ref "C3") (pin "PAD_1") (pinfunction "PIN1_PAD_1") (pintype "bidirectional"))
      (node (ref "IC1") (pin "29") (pinfunction "AREF_29") (pintype "passive"))
    )
    (net (code "25") (name "Net-(C16-PIN0)") (class "Default")
      (node (ref "C16") (pin "PAD_0") (pinfunction "PIN0_PAD_0") (pintype "bidirectional"))
      (node (ref "IC7") (pin "1") (pinfunction "OUT_1") (pintype "output"))
      (node (ref "R54") (pin "PAD_1") (pinfunction "PIN1_PAD_1") (pintype "passive"))
      (node (ref "R59") (pin "PAD_0") (pinfunction "PIN0_PAD_0") (pintype "passive"))
    )
    (net (code "26") (name "Net-(C16-PIN1)") (class "Default")
      (node (ref "C16") (pin "PAD_1") (pinfunction "PIN1_PAD_1") (pintype "bidirectional"))
      (node (ref "IC7") (pin "2") (pinfunction "IN-_2") (pintype "input"))
      (node (ref "R54") (pin "PAD_0") (pinfunction "PIN0_PAD_0") (pintype "passive"))
      (node (ref "R58") (pin "PAD_1") (pinfunction "PIN1_PAD_1") (pintype "passive"))
    )
    (net (code "27") (name "Net-(C17-PIN0)") (class "Default")
      (node (ref "C17") (pin "PAD_0") (pinfunction "PIN0_PAD_0") (pintype "bidirectional"))
      (node (ref "R55") (pin "PAD_1") (pinfunction "PIN1_PAD_1") (pintype "passive"))
      (node (ref "T1") (pin "1") (pinfunction "B_1") (pintype "bidirectional"))
      (node (ref "T2") (pin "1") (pinfunction "B_1") (pintype "bidirectional"))
    )
    (net (code "28") (name "Net-(C19-PIN1)") (class "Default")
      (node (ref "C18") (pin "-") (pinfunction "-_-") (pintype "bidirectional"))
      (node (ref "C19") (pin "PAD_1") (pinfunction "PIN1_PAD_1") (pintype "bidirectional"))
      (node (ref "R57") (pin "PAD_1") (pinfunction "PIN1_PAD_1") (pintype "passive"))
      (node (ref "R58") (pin "PAD_0") (pinfunction "PIN0_PAD_0") (pintype "passive"))
      (node (ref "R60") (pin "PAD_0") (pinfunction "PIN0_PAD_0") (pintype "passive"))
    )
    (net (code "29") (name "Net-(C22-PIN0)") (class "Default")
      (node (ref "C22") (pin "PAD_0") (pinfunction "PIN0_PAD_0") (pintype "bidirectional"))
      (node (ref "D14") (pin "ANODE") (pinfunction "ANODE_ANODE") (pintype "passive"))
      (node (ref "D18") (pin "CATHODE") (pinfunction "CATHODE_CATHODE") (pintype "passive"))
    )
    (net (code "30") (name "Net-(C22-PIN1)") (class "Default")
      (node (ref "C22") (pin "PAD_1") (pinfunction "PIN1_PAD_1") (pintype "bidirectional"))
      (node (ref "C42") (pin "PAD_1") (pinfunction "PIN1_PAD_1") (pintype "bidirectional"))
      (node (ref "R68") (pin "PAD_0") (pinfunction "PIN0_PAD_0") (pintype "passive"))
      (node (ref "T4") (pin "3") (pinfunction "C_3") (pintype "bidirectional"))
    )
    (net (code "31") (name "Net-(C23-PIN0)") (class "Default")
      (node (ref "C23") (pin "PAD_0") (pinfunction "PIN0_PAD_0") (pintype "bidirectional"))
      (node (ref "D15") (pin "ANODE") (pinfunction "ANODE_ANODE") (pintype "passive"))
      (node (ref "D20") (pin "CATHODE") (pinfunction "CATHODE_CATHODE") (pintype "passive"))
    )
    (net (code "32") (name "Net-(C23-PIN1)") (class "Default")
      (node (ref "C23") (pin "PAD_1") (pinfunction "PIN1_PAD_1") (pintype "bidirectional"))
      (node (ref "C43") (pin "PAD_1") (pinfunction "PIN1_PAD_1") (pintype "bidirectional"))
      (node (ref "R70") (pin "PAD_0") (pinfunction "PIN0_PAD_0") (pintype "passive"))
      (node (ref "T5") (pin "3") (pinfunction "C_3") (pintype "bidirectional"))
    )
    (net (code "33") (name "Net-(C24-PIN0)") (class "Default")
      (node (ref "C24") (pin "PAD_0") (pinfunction "PIN0_PAD_0") (pintype "bidirectional"))
      (node (ref "D16") (pin "ANODE") (pinfunction "ANODE_ANODE") (pintype "passive"))
      (node (ref "D22") (pin "CATHODE") (pinfunction "CATHODE_CATHODE") (pintype "passive"))
    )
    (net (code "34") (name "Net-(C24-PIN1)") (class "Default")
      (node (ref "C24") (pin "PAD_1") (pinfunction "PIN1_PAD_1") (pintype "bidirectional"))
      (node (ref "R72") (pin "PAD_0") (pinfunction "PIN0_PAD_0") (pintype "passive"))
      (node (ref "T6") (pin "3") (pinfunction "C_3") (pintype "bidirectional"))
    )
    (net (code "35") (name "Net-(C28-PIN1)") (class "Default")
      (node (ref "C27") (pin "+") (pinfunction "+_+") (pintype "bidirectional"))
      (node (ref "C28") (pin "PAD_1") (pinfunction "PIN1_PAD_1") (pintype "bidirectional"))
      (node (ref "D14") (pin "CATHODE") (pinfunction "CATHODE_CATHODE") (pintype "passive"))
      (node (ref "R61") (pin "PAD_0") (pinfunction "PIN0_PAD_0") (pintype "passive"))
      (node (ref "R86") (pin "PAD_1") (pinfunction "PIN1_PAD_1") (pintype "passive"))
    )
    (net (code "36") (name "Net-(C31-PIN1)") (class "Default")
      (node (ref "C30") (pin "+") (pinfunction "+_+") (pintype "bidirectional"))
      (node (ref "C31") (pin "PAD_1") (pinfunction "PIN1_PAD_1") (pintype "bidirectional"))
      (node (ref "D15") (pin "CATHODE") (pinfunction "CATHODE_CATHODE") (pintype "passive"))
      (node (ref "R62") (pin "PAD_0") (pinfunction "PIN0_PAD_0") (pintype "passive"))
      (node (ref "R87") (pin "PAD_1") (pinfunction "PIN1_PAD_1") (pintype "passive"))
    )
    (net (code "37") (name "Net-(C34-PIN1)") (class "Default")
      (node (ref "C33") (pin "+") (pinfunction "+_+") (pintype "bidirectional"))
      (node (ref "C34") (pin "PAD_1") (pinfunction "PIN1_PAD_1") (pintype "bidirectional"))
      (node (ref "D16") (pin "CATHODE") (pinfunction "CATHODE_CATHODE") (pintype "passive"))
      (node (ref "R63") (pin "PAD_0") (pinfunction "PIN0_PAD_0") (pintype "passive"))
      (node (ref "R88") (pin "PAD_1") (pinfunction "PIN1_PAD_1") (pintype "passive"))
    )
    (net (code "38") (name "Net-(C35-PIN0)") (class "Default")
      (node (ref "C35") (pin "PAD_0") (pinfunction "PIN0_PAD_0") (pintype "bidirectional"))
      (node (ref "R64") (pin "PAD_1") (pinfunction "PIN1_PAD_1") (pintype "passive"))
      (node (ref "R67") (pin "PAD_1") (pinfunction "PIN1_PAD_1") (pintype "passive"))
      (node (ref "R68") (pin "PAD_1") (pinfunction "PIN1_PAD_1") (pintype "passive"))
    )
    (net (code "39") (name "Net-(C36-PIN0)") (class "Default")
      (node (ref "C36") (pin "PAD_0") (pinfunction "PIN0_PAD_0") (pintype "bidirectional"))
      (node (ref "R65") (pin "PAD_1") (pinfunction "PIN1_PAD_1") (pintype "passive"))
      (node (ref "R69") (pin "PAD_1") (pinfunction "PIN1_PAD_1") (pintype "passive"))
      (node (ref "R70") (pin "PAD_1") (pinfunction "PIN1_PAD_1") (pintype "passive"))
    )
    (net (code "40") (name "Net-(C37-PIN0)") (class "Default")
      (node (ref "C37") (pin "PAD_0") (pinfunction "PIN0_PAD_0") (pintype "bidirectional"))
      (node (ref "R66") (pin "PAD_1") (pinfunction "PIN1_PAD_1") (pintype "passive"))
      (node (ref "R71") (pin "PAD_1") (pinfunction "PIN1_PAD_1") (pintype "passive"))
      (node (ref "R72") (pin "PAD_1") (pinfunction "PIN1_PAD_1") (pintype "passive"))
    )
    (net (code "41") (name "Net-(C39-PIN0)") (class "Default")
      (node (ref "C39") (pin "PAD_0") (pinfunction "PIN0_PAD_0") (pintype "bidirectional"))
      (node (ref "R74") (pin "PAD_1") (pinfunction "PIN1_PAD_1") (pintype "passive"))
      (node (ref "T3") (pin "1") (pinfunction "B_1") (pintype "bidirectional"))
      (node (ref "T7") (pin "1") (pinfunction "B_1") (pintype "bidirectional"))
    )
    (net (code "42") (name "Net-(C40-PIN0)") (class "Default")
      (node (ref "C40") (pin "PAD_0") (pinfunction "PIN0_PAD_0") (pintype "bidirectional"))
      (node (ref "C41") (pin "PAD_1") (pinfunction "PIN1_PAD_1") (pintype "bidirectional"))
      (node (ref "D25") (pin "CATHODE") (pinfunction "CATHODE_CATHODE") (pintype "passive"))
      (node (ref "D26") (pin "ANODE") (pinfunction "ANODE_ANODE") (pintype "passive"))
      (node (ref "X3") (pin "1") (pinfunction "KL_1") (pintype "passive"))
    )
    (net (code "43") (name "Net-(C40-PIN1)") (class "Default")
      (node (ref "C40") (pin "PAD_1") (pinfunction "PIN1_PAD_1") (pintype "bidirectional"))
      (node (ref "C44") (pin "PAD_1") (pinfunction "PIN1_PAD_1") (pintype "bidirectional"))
      (node (ref "R73") (pin "PAD_1") (pinfunction "PIN1_PAD_1") (pintype "passive"))
    )
    (net (code "44") (name "Net-(C41-PIN0)") (class "Default")
      (node (ref "C41") (pin "PAD_0") (pinfunction "PIN0_PAD_0") (pintype "bidirectional"))
      (node (ref "R67") (pin "PAD_0") (pinfunction "PIN0_PAD_0") (pintype "passive"))
      (node (ref "R75") (pin "PAD_1") (pinfunction "PIN1_PAD_1") (pintype "passive"))
      (node (ref "T4") (pin "1") (pinfunction "B_1") (pintype "bidirectional"))
    )
    (net (code "45") (name "Net-(C42-PIN0)") (class "Default")
      (node (ref "C42") (pin "PAD_0") (pinfunction "PIN0_PAD_0") (pintype "bidirectional"))
      (node (ref "R69") (pin "PAD_0") (pinfunction "PIN0_PAD_0") (pintype "passive"))
      (node (ref "R77") (pin "PAD_1") (pinfunction "PIN1_PAD_1") (pintype "passive"))
      (node (ref "T5") (pin "1") (pinfunction "B_1") (pintype "bidirectional"))
    )
    (net (code "46") (name "Net-(C43-PIN0)") (class "Default")
      (node (ref "C43") (pin "PAD_0") (pinfunction "PIN0_PAD_0") (pintype "bidirectional"))
      (node (ref "R71") (pin "PAD_0") (pinfunction "PIN0_PAD_0") (pintype "passive"))
      (node (ref "R79") (pin "PAD_1") (pinfunction "PIN1_PAD_1") (pintype "passive"))
      (node (ref "T6") (pin "1") (pinfunction "B_1") (pintype "bidirectional"))
    )
    (net (code "47") (name "Net-(C45-PIN1)") (class "Default")
      (node (ref "C45") (pin "PAD_1") (pinfunction "PIN1_PAD_1") (pintype "bidirectional"))
      (node (ref "C46") (pin "-") (pinfunction "-_-") (pintype "bidirectional"))
      (node (ref "D27") (pin "ANODE") (pinfunction "ANODE_ANODE") (pintype "passive"))
      (node (ref "IC8") (pin "2") (pinfunction "IN_2") (pintype "input"))
    )
    (net (code "48") (name "Net-(C49-PIN1)") (class "Default")
      (node (ref "C49") (pin "PAD_1") (pinfunction "PIN1_PAD_1") (pintype "bidirectional"))
      (node (ref "C50") (pin "+") (pinfunction "+_+") (pintype "bidirectional"))
      (node (ref "D28") (pin "CATHODE") (pinfunction "CATHODE_CATHODE") (pintype "passive"))
      (node (ref "IC9") (pin "3") (pinfunction "IN_3") (pintype "input"))
    )
    (net (code "49") (name "Net-(C55-PIN1)") (class "Default")
      (node (ref "C55") (pin "PAD_1") (pinfunction "PIN1_PAD_1") (pintype "bidirectional"))
      (node (ref "IC10") (pin "3") (pinfunction "CT_3") (pintype "bidirectional"))
    )
    (net (code "50") (name "Net-(IC1-(ADC0)PA0)") (class "Default")
      (node (ref "IC1") (pin "37") (pinfunction "(ADC0)PA0_37") (pintype "bidirectional"))
      (node (ref "J100") (pin "PAD_1") (pinfunction "PIN1_PAD_1") (pintype "passive"))
    )
    (net (code "51") (name "Net-(IC1-(INT0)PD2)") (class "Default")
      (node (ref "IC1") (pin "11") (pinfunction "(INT0)PD2_11") (pintype "bidirectional"))
      (node (ref "R9") (pin "PAD_1") (pinfunction "PIN1_PAD_1") (pintype "passive"))
    )
    (net (code "52") (name "Net-(IC1-(INT1)PD3)") (class "Default")
      (node (ref "IC1") (pin "12") (pinfunction "(INT1)PD3_12") (pintype "bidirectional"))
      (node (ref "R8") (pin "PAD_1") (pinfunction "PIN1_PAD_1") (pintype "passive"))
    )
    (net (code "53") (name "Net-(IC1-(TXD)PD1)") (class "Default")
      (node (ref "IC1") (pin "10") (pinfunction "(TXD)PD1_10") (pintype "bidirectional"))
      (node (ref "R10") (pin "PAD_0") (pinfunction "PIN0_PAD_0") (pintype "passive"))
    )
    (net (code "54") (name "Net-(IC2-LATCH)") (class "Default")
      (node (ref "D1") (pin "ANODE") (pinfunction "ANODE_ANODE") (pintype "passive"))
      (node (ref "IC2") (pin "12") (pinfunction "LATCH_12") (pintype "bidirectional"))
      (node (ref "J10") (pin "PAD_0") (pinfunction "PIN0_PAD_0") (pintype "passive"))
      (node (ref "J4") (pin "PAD_0") (pinfunction "PIN0_PAD_0") (pintype "passive"))
      (node (ref "J6") (pin "PAD_0") (pinfunction "PIN0_PAD_0") (pintype "passive"))
      (node (ref "J8") (pin "PAD_0") (pinfunction "PIN0_PAD_0") (pintype "passive"))
      (node (ref "R21") (pin "PAD_1") (pinfunction "PIN1_PAD_1") (pintype "passive"))
    )
    (net (code "55") (name "Net-(IC2-QA)") (class "Default")
      (node (ref "IC2") (pin "15") (pinfunction "QA_15") (pintype "bidirectional"))
      (node (ref "R11") (pin "PAD_0") (pinfunction "PIN0_PAD_0") (pintype "passive"))
    )
    (net (code "56") (name "Net-(IC2-QB)") (class "Default")
      (node (ref "IC2") (pin "1") (pinfunction "QB_1") (pintype "bidirectional"))
      (node (ref "R12") (pin "PAD_0") (pinfunction "PIN0_PAD_0") (pintype "passive"))
    )
    (net (code "57") (name "Net-(IC2-QC)") (class "Default")
      (node (ref "IC2") (pin "2") (pinfunction "QC_2") (pintype "bidirectional"))
      (node (ref "R13") (pin "PAD_0") (pinfunction "PIN0_PAD_0") (pintype "passive"))
    )
    (net (code "58") (name "Net-(IC2-QD)") (class "Default")
      (node (ref "IC2") (pin "3") (pinfunction "QD_3") (pintype "bidirectional"))
      (node (ref "R14") (pin "PAD_0") (pinfunction "PIN0_PAD_0") (pintype "passive"))
    )
    (net (code "59") (name "Net-(IC2-QE)") (class "Default")
      (node (ref "IC2") (pin "4") (pinfunction "QE_4") (pintype "bidirectional"))
      (node (ref "R15") (pin "PAD_0") (pinfunction "PIN0_PAD_0") (pintype "passive"))
    )
    (net (code "60") (name "Net-(IC2-QF)") (class "Default")
      (node (ref "IC2") (pin "5") (pinfunction "QF_5") (pintype "bidirectional"))
      (node (ref "R16") (pin "PAD_0") (pinfunction "PIN0_PAD_0") (pintype "passive"))
    )
    (net (code "61") (name "Net-(IC2-QG)") (class "Default")
      (node (ref "IC2") (pin "6") (pinfunction "QG_6") (pintype "bidirectional"))
      (node (ref "R18") (pin "PAD_0") (pinfunction "PIN0_PAD_0") (pintype "passive"))
    )
    (net (code "62") (name "Net-(IC2-QH)") (class "Default")
      (node (ref "IC2") (pin "7") (pinfunction "QH_7") (pintype "bidirectional"))
      (node (ref "R20") (pin "PAD_0") (pinfunction "PIN0_PAD_0") (pintype "passive"))
    )
    (net (code "63") (name "Net-(IC2-SER_CLK)") (class "Default")
      (node (ref "D2") (pin "ANODE") (pinfunction "ANODE_ANODE") (pintype "passive"))
      (node (ref "IC2") (pin "11") (pinfunction "SER_CLK_11") (pintype "bidirectional"))
      (node (ref "IC3") (pin "11") (pinfunction "SER_CLK_11") (pintype "bidirectional"))
      (node (ref "IC4") (pin "11") (pinfunction "SER_CLK_11") (pintype "bidirectional"))
      (node (ref "IC5") (pin "11") (pinfunction "SER_CLK_11") (pintype "bidirectional"))
      (node (ref "IC6") (pin "11") (pinfunction "SER_CLK_11") (pintype "bidirectional"))
      (node (ref "R19") (pin "PAD_1") (pinfunction "PIN1_PAD_1") (pintype "passive"))
    )
    (net (code "64") (name "Net-(IC2-SER_IN)") (class "Default")
      (node (ref "D3") (pin "ANODE") (pinfunction "ANODE_ANODE") (pintype "passive"))
      (node (ref "IC2") (pin "14") (pinfunction "SER_IN_14") (pintype "bidirectional"))
      (node (ref "R17") (pin "PAD_1") (pinfunction "PIN1_PAD_1") (pintype "passive"))
    )
    (net (code "65") (name "Net-(IC2-SER_OUT)") (class "Default")
      (node (ref "IC2") (pin "9") (pinfunction "SER_OUT_9") (pintype "bidirectional"))
      (node (ref "IC3") (pin "14") (pinfunction "SER_IN_14") (pintype "bidirectional"))
    )
    (net (code "66") (name "Net-(IC3-LATCH)") (class "Default")
      (node (ref "IC3") (pin "12") (pinfunction "LATCH_12") (pintype "bidirectional"))
      (node (ref "J4") (pin "PAD_1") (pinfunction "PIN1_PAD_1") (pintype "passive"))
    )
    (net (code "67") (name "Net-(IC3-QA)") (class "Default")
      (node (ref "IC3") (pin "15") (pinfunction "QA_15") (pintype "bidirectional"))
      (node (ref "R22") (pin "PAD_0") (pinfunction "PIN0_PAD_0") (pintype "passive"))
    )
    (net (code "68") (name "Net-(IC3-QB)") (class "Default")
      (node (ref "IC3") (pin "1") (pinfunction "QB_1") (pintype "bidirectional"))
      (node (ref "R23") (pin "PAD_0") (pinfunction "PIN0_PAD_0") (pintype "passive"))
    )
    (net (code "69") (name "Net-(IC3-QC)") (class "Default")
      (node (ref "IC3") (pin "2") (pinfunction "QC_2") (pintype "bidirectional"))
      (node (ref "R24") (pin "PAD_0") (pinfunction "PIN0_PAD_0") (pintype "passive"))
    )
    (net (code "70") (name "Net-(IC3-QD)") (class "Default")
      (node (ref "IC3") (pin "3") (pinfunction "QD_3") (pintype "bidirectional"))
      (node (ref "R25") (pin "PAD_0") (pinfunction "PIN0_PAD_0") (pintype "passive"))
    )
    (net (code "71") (name "Net-(IC3-QE)") (class "Default")
      (node (ref "IC3") (pin "4") (pinfunction "QE_4") (pintype "bidirectional"))
      (node (ref "R26") (pin "PAD_0") (pinfunction "PIN0_PAD_0") (pintype "passive"))
    )
    (net (code "72") (name "Net-(IC3-QF)") (class "Default")
      (node (ref "IC3") (pin "5") (pinfunction "QF_5") (pintype "bidirectional"))
      (node (ref "R27") (pin "PAD_0") (pinfunction "PIN0_PAD_0") (pintype "passive"))
    )
    (net (code "73") (name "Net-(IC3-QG)") (class "Default")
      (node (ref "IC3") (pin "6") (pinfunction "QG_6") (pintype "bidirectional"))
      (node (ref "R28") (pin "PAD_0") (pinfunction "PIN0_PAD_0") (pintype "passive"))
    )
    (net (code "74") (name "Net-(IC3-QH)") (class "Default")
      (node (ref "IC3") (pin "7") (pinfunction "QH_7") (pintype "bidirectional"))
      (node (ref "R29") (pin "PAD_0") (pinfunction "PIN0_PAD_0") (pintype "passive"))
    )
    (net (code "75") (name "Net-(IC3-SER_OUT)") (class "Default")
      (node (ref "IC3") (pin "9") (pinfunction "SER_OUT_9") (pintype "bidirectional"))
      (node (ref "IC4") (pin "14") (pinfunction "SER_IN_14") (pintype "bidirectional"))
    )
    (net (code "76") (name "Net-(IC4-LATCH)") (class "Default")
      (node (ref "IC4") (pin "12") (pinfunction "LATCH_12") (pintype "bidirectional"))
      (node (ref "J6") (pin "PAD_1") (pinfunction "PIN1_PAD_1") (pintype "passive"))
    )
    (net (code "77") (name "Net-(IC4-QA)") (class "Default")
      (node (ref "IC4") (pin "15") (pinfunction "QA_15") (pintype "bidirectional"))
      (node (ref "R30") (pin "PAD_0") (pinfunction "PIN0_PAD_0") (pintype "passive"))
    )
    (net (code "78") (name "Net-(IC4-QB)") (class "Default")
      (node (ref "IC4") (pin "1") (pinfunction "QB_1") (pintype "bidirectional"))
      (node (ref "R31") (pin "PAD_0") (pinfunction "PIN0_PAD_0") (pintype "passive"))
    )
    (net (code "79") (name "Net-(IC4-QC)") (class "Default")
      (node (ref "IC4") (pin "2") (pinfunction "QC_2") (pintype "bidirectional"))
      (node (ref "R32") (pin "PAD_0") (pinfunction "PIN0_PAD_0") (pintype "passive"))
    )
    (net (code "80") (name "Net-(IC4-QD)") (class "Default")
      (node (ref "IC4") (pin "3") (pinfunction "QD_3") (pintype "bidirectional"))
      (node (ref "R33") (pin "PAD_0") (pinfunction "PIN0_PAD_0") (pintype "passive"))
    )
    (net (code "81") (name "Net-(IC4-QE)") (class "Default")
      (node (ref "IC4") (pin "4") (pinfunction "QE_4") (pintype "bidirectional"))
      (node (ref "R34") (pin "PAD_0") (pinfunction "PIN0_PAD_0") (pintype "passive"))
    )
    (net (code "82") (name "Net-(IC4-QF)") (class "Default")
      (node (ref "IC4") (pin "5") (pinfunction "QF_5") (pintype "bidirectional"))
      (node (ref "R35") (pin "PAD_0") (pinfunction "PIN0_PAD_0") (pintype "passive"))
    )
    (net (code "83") (name "Net-(IC4-QG)") (class "Default")
      (node (ref "IC4") (pin "6") (pinfunction "QG_6") (pintype "bidirectional"))
      (node (ref "R36") (pin "PAD_0") (pinfunction "PIN0_PAD_0") (pintype "passive"))
    )
    (net (code "84") (name "Net-(IC4-QH)") (class "Default")
      (node (ref "IC4") (pin "7") (pinfunction "QH_7") (pintype "bidirectional"))
      (node (ref "R37") (pin "PAD_0") (pinfunction "PIN0_PAD_0") (pintype "passive"))
    )
    (net (code "85") (name "Net-(IC4-SER_OUT)") (class "Default")
      (node (ref "IC4") (pin "9") (pinfunction "SER_OUT_9") (pintype "bidirectional"))
      (node (ref "IC5") (pin "14") (pinfunction "SER_IN_14") (pintype "bidirectional"))
    )
    (net (code "86") (name "Net-(IC5-LATCH)") (class "Default")
      (node (ref "IC5") (pin "12") (pinfunction "LATCH_12") (pintype "bidirectional"))
      (node (ref "J8") (pin "PAD_1") (pinfunction "PIN1_PAD_1") (pintype "passive"))
    )
    (net (code "87") (name "Net-(IC5-QA)") (class "Default")
      (node (ref "IC5") (pin "15") (pinfunction "QA_15") (pintype "bidirectional"))
      (node (ref "R38") (pin "PAD_0") (pinfunction "PIN0_PAD_0") (pintype "passive"))
    )
    (net (code "88") (name "Net-(IC5-QB)") (class "Default")
      (node (ref "IC5") (pin "1") (pinfunction "QB_1") (pintype "bidirectional"))
      (node (ref "R39") (pin "PAD_0") (pinfunction "PIN0_PAD_0") (pintype "passive"))
    )
    (net (code "89") (name "Net-(IC5-QC)") (class "Default")
      (node (ref "IC5") (pin "2") (pinfunction "QC_2") (pintype "bidirectional"))
      (node (ref "R40") (pin "PAD_0") (pinfunction "PIN0_PAD_0") (pintype "passive"))
    )
    (net (code "90") (name "Net-(IC5-QD)") (class "Default")
      (node (ref "IC5") (pin "3") (pinfunction "QD_3") (pintype "bidirectional"))
      (node (ref "R41") (pin "PAD_0") (pinfunction "PIN0_PAD_0") (pintype "passive"))
    )
    (net (code "91") (name "Net-(IC5-QE)") (class "Default")
      (node (ref "IC5") (pin "4") (pinfunction "QE_4") (pintype "bidirectional"))
      (node (ref "R42") (pin "PAD_0") (pinfunction "PIN0_PAD_0") (pintype "passive"))
    )
    (net (code "92") (name "Net-(IC5-QF)") (class "Default")
      (node (ref "IC5") (pin "5") (pinfunction "QF_5") (pintype "bidirectional"))
      (node (ref "R43") (pin "PAD_0") (pinfunction "PIN0_PAD_0") (pintype "passive"))
    )
    (net (code "93") (name "Net-(IC5-QG)") (class "Default")
      (node (ref "IC5") (pin "6") (pinfunction "QG_6") (pintype "bidirectional"))
      (node (ref "R44") (pin "PAD_0") (pinfunction "PIN0_PAD_0") (pintype "passive"))
    )
    (net (code "94") (name "Net-(IC5-QH)") (class "Default")
      (node (ref "IC5") (pin "7") (pinfunction "QH_7") (pintype "bidirectional"))
      (node (ref "R45") (pin "PAD_0") (pinfunction "PIN0_PAD_0") (pintype "passive"))
    )
    (net (code "95") (name "Net-(IC5-SER_OUT)") (class "Default")
      (node (ref "IC5") (pin "9") (pinfunction "SER_OUT_9") (pintype "bidirectional"))
      (node (ref "IC6") (pin "14") (pinfunction "SER_IN_14") (pintype "bidirectional"))
    )
    (net (code "96") (name "Net-(IC6-LATCH)") (class "Default")
      (node (ref "IC6") (pin "12") (pinfunction "LATCH_12") (pintype "bidirectional"))
      (node (ref "J10") (pin "PAD_1") (pinfunction "PIN1_PAD_1") (pintype "passive"))
    )
    (net (code "97") (name "Net-(IC6-QA)") (class "Default")
      (node (ref "IC6") (pin "15") (pinfunction "QA_15") (pintype "bidirectional"))
      (node (ref "R46") (pin "PAD_0") (pinfunction "PIN0_PAD_0") (pintype "passive"))
    )
    (net (code "98") (name "Net-(IC6-QB)") (class "Default")
      (node (ref "IC6") (pin "1") (pinfunction "QB_1") (pintype "bidirectional"))
      (node (ref "R47") (pin "PAD_0") (pinfunction "PIN0_PAD_0") (pintype "passive"))
    )
    (net (code "99") (name "Net-(IC6-QC)") (class "Default")
      (node (ref "IC6") (pin "2") (pinfunction "QC_2") (pintype "bidirectional"))
      (node (ref "R48") (pin "PAD_0") (pinfunction "PIN0_PAD_0") (pintype "passive"))
    )
    (net (code "100") (name "Net-(IC6-QD)") (class "Default")
      (node (ref "IC6") (pin "3") (pinfunction "QD_3") (pintype "bidirectional"))
      (node (ref "R49") (pin "PAD_0") (pinfunction "PIN0_PAD_0") (pintype "passive"))
    )
    (net (code "101") (name "Net-(IC6-QE)") (class "Default")
      (node (ref "IC6") (pin "4") (pinfunction "QE_4") (pintype "bidirectional"))
      (node (ref "R50") (pin "PAD_0") (pinfunction "PIN0_PAD_0") (pintype "passive"))
    )
    (net (code "102") (name "Net-(IC6-QF)") (class "Default")
      (node (ref "IC6") (pin "5") (pinfunction "QF_5") (pintype "bidirectional"))
      (node (ref "R51") (pin "PAD_0") (pinfunction "PIN0_PAD_0") (pintype "passive"))
    )
    (net (code "103") (name "Net-(IC6-QG)") (class "Default")
      (node (ref "IC6") (pin "6") (pinfunction "QG_6") (pintype "bidirectional"))
      (node (ref "R52") (pin "PAD_0") (pinfunction "PIN0_PAD_0") (pintype "passive"))
    )
    (net (code "104") (name "Net-(IC6-QH)") (class "Default")
      (node (ref "IC6") (pin "7") (pinfunction "QH_7") (pintype "bidirectional"))
      (node (ref "R53") (pin "PAD_0") (pinfunction "PIN0_PAD_0") (pintype "passive"))
    )
    (net (code "105") (name "Net-(IC7B-IN-)") (class "Default")
      (node (ref "IC7") (pin "6") (pinfunction "IN-_6") (pintype "input"))
      (node (ref "IC7") (pin "7") (pinfunction "OUT_7") (pintype "output"))
    )
    (net (code "106") (name "Net-(IC7C-IN-)") (class "Default")
      (node (ref "IC7") (pin "8") (pinfunction "OUT_8") (pintype "output"))
      (node (ref "IC7") (pin "9") (pinfunction "IN-_9") (pintype "input"))
    )
    (net (code "107") (name "Net-(IC7D-IN-)") (class "Default")
      (node (ref "IC7") (pin "13") (pinfunction "IN-_13") (pintype "input"))
      (node (ref "IC7") (pin "14") (pinfunction "OUT_14") (pintype "output"))
    )
    (net (code "108") (name "Net-(IC9-ADJ)") (class "Default")
      (node (ref "IC9") (pin "1") (pinfunction "ADJ_1") (pintype "input"))
      (node (ref "R81") (pin "PAD_1") (pinfunction "PIN1_PAD_1") (pintype "passive"))
      (node (ref "R82") (pin "PAD_1") (pinfunction "PIN1_PAD_1") (pintype "passive"))
      (node (ref "R90") (pin "PAD_1") (pinfunction "PIN1_PAD_1") (pintype "passive"))
    )
    (net (code "109") (name "Net-(IC10-DR_C)") (class "Default")
      (node (ref "IC10") (pin "1") (pinfunction "SW_C_1") (pintype "bidirectional"))
      (node (ref "IC10") (pin "7") (pinfunction "I_PEAK_7") (pintype "bidirectional"))
      (node (ref "IC10") (pin "8") (pinfunction "DR_C_8") (pintype "bidirectional"))
      (node (ref "R83") (pin "PAD_1") (pinfunction "PIN1_PAD_1") (pintype "passive"))
    )
    (net (code "110") (name "Net-(IC10-INV_IN)") (class "Default")
      (node (ref "IC10") (pin "5") (pinfunction "INV_IN_5") (pintype "bidirectional"))
      (node (ref "R84") (pin "PAD_0") (pinfunction "PIN0_PAD_0") (pintype "passive"))
      (node (ref "R85") (pin "PAD_1") (pinfunction "PIN1_PAD_1") (pintype "passive"))
    )
    (net (code "111") (name "Net-(IC10-SW_E)") (class "Default")
      (node (ref "D27") (pin "CATHODE") (pinfunction "CATHODE_CATHODE") (pintype "passive"))
      (node (ref "IC10") (pin "2") (pinfunction "SW_E_2") (pintype "bidirectional"))
      (node (ref "TR1") (pin "W1_END") (pinfunction "PRI_END_W1_END") (pintype "bidirectional"))
    )
    (net (code "112") (name "Net-(J11-PIN0)") (class "Default")
      (node (ref "J11") (pin "PAD_0") (pinfunction "PIN0_PAD_0") (pintype "passive"))
      (node (ref "X4") (pin "2") (pinfunction "D-_2") (pintype "bidirectional"))
    )
    (net (code "113") (name "Net-(LI1-A)") (class "Default")
      (node (ref "LI1") (pin "7") (pinfunction "A_7") (pintype "passive"))
      (node (ref "R15") (pin "PAD_1") (pinfunction "PIN1_PAD_1") (pintype "passive"))
    )
    (net (code "114") (name "Net-(LI1-B)") (class "Default")
      (node (ref "LI1") (pin "6") (pinfunction "B_6") (pintype "passive"))
      (node (ref "R18") (pin "PAD_1") (pinfunction "PIN1_PAD_1") (pintype "passive"))
    )
    (net (code "115") (name "Net-(LI1-C)") (class "Default")
      (node (ref "LI1") (pin "4") (pinfunction "C_4") (pintype "passive"))
      (node (ref "R16") (pin "PAD_1") (pinfunction "PIN1_PAD_1") (pintype "passive"))
    )
    (net (code "116") (name "Net-(LI1-D)") (class "Default")
      (node (ref "LI1") (pin "2") (pinfunction "D_2") (pintype "passive"))
      (node (ref "R13") (pin "PAD_1") (pinfunction "PIN1_PAD_1") (pintype "passive"))
    )
    (net (code "117") (name "Net-(LI1-DOT)") (class "Default")
      (node (ref "LI1") (pin "5") (pinfunction "DOT_5") (pintype "passive"))
      (node (ref "R20") (pin "PAD_1") (pinfunction "PIN1_PAD_1") (pintype "passive"))
    )
    (net (code "118") (name "Net-(LI1-E)") (class "Default")
      (node (ref "LI1") (pin "1") (pinfunction "E_1") (pintype "passive"))
      (node (ref "R11") (pin "PAD_1") (pinfunction "PIN1_PAD_1") (pintype "passive"))
    )
    (net (code "119") (name "Net-(LI1-F)") (class "Default")
      (node (ref "LI1") (pin "9") (pinfunction "F_9") (pintype "passive"))
      (node (ref "R14") (pin "PAD_1") (pinfunction "PIN1_PAD_1") (pintype "passive"))
    )
    (net (code "120") (name "Net-(LI1-G)") (class "Default")
      (node (ref "LI1") (pin "10") (pinfunction "G_10") (pintype "passive"))
      (node (ref "R12") (pin "PAD_1") (pinfunction "PIN1_PAD_1") (pintype "passive"))
    )
    (net (code "121") (name "Net-(LI2-A)") (class "Default")
      (node (ref "LI2") (pin "7") (pinfunction "A_7") (pintype "passive"))
      (node (ref "R26") (pin "PAD_1") (pinfunction "PIN1_PAD_1") (pintype "passive"))
    )
    (net (code "122") (name "Net-(LI2-B)") (class "Default")
      (node (ref "LI2") (pin "6") (pinfunction "B_6") (pintype "passive"))
      (node (ref "R28") (pin "PAD_1") (pinfunction "PIN1_PAD_1") (pintype "passive"))
    )
    (net (code "123") (name "Net-(LI2-C)") (class "Default")
      (node (ref "LI2") (pin "4") (pinfunction "C_4") (pintype "passive"))
      (node (ref "R27") (pin "PAD_1") (pinfunction "PIN1_PAD_1") (pintype "passive"))
    )
    (net (code "124") (name "Net-(LI2-D)") (class "Default")
      (node (ref "LI2") (pin "2") (pinfunction "D_2") (pintype "passive"))
      (node (ref "R24") (pin "PAD_1") (pinfunction "PIN1_PAD_1") (pintype "passive"))
    )
    (net (code "125") (name "Net-(LI2-DOT)") (class "Default")
      (node (ref "LI2") (pin "5") (pinfunction "DOT_5") (pintype "passive"))
      (node (ref "R29") (pin "PAD_1") (pinfunction "PIN1_PAD_1") (pintype "passive"))
    )
    (net (code "126") (name "Net-(LI2-E)") (class "Default")
      (node (ref "LI2") (pin "1") (pinfunction "E_1") (pintype "passive"))
      (node (ref "R22") (pin "PAD_1") (pinfunction "PIN1_PAD_1") (pintype "passive"))
    )
    (net (code "127") (name "Net-(LI2-F)") (class "Default")
      (node (ref "LI2") (pin "9") (pinfunction "F_9") (pintype "passive"))
      (node (ref "R25") (pin "PAD_1") (pinfunction "PIN1_PAD_1") (pintype "passive"))
    )
    (net (code "128") (name "Net-(LI2-G)") (class "Default")
      (node (ref "LI2") (pin "10") (pinfunction "G_10") (pintype "passive"))
      (node (ref "R23") (pin "PAD_1") (pinfunction "PIN1_PAD_1") (pintype "passive"))
    )
    (net (code "129") (name "Net-(LI3-A)") (class "Default")
      (node (ref "LI3") (pin "7") (pinfunction "A_7") (pintype "passive"))
      (node (ref "R34") (pin "PAD_1") (pinfunction "PIN1_PAD_1") (pintype "passive"))
    )
    (net (code "130") (name "Net-(LI3-B)") (class "Default")
      (node (ref "LI3") (pin "6") (pinfunction "B_6") (pintype "passive"))
      (node (ref "R36") (pin "PAD_1") (pinfunction "PIN1_PAD_1") (pintype "passive"))
    )
    (net (code "131") (name "Net-(LI3-C)") (class "Default")
      (node (ref "LI3") (pin "4") (pinfunction "C_4") (pintype "passive"))
      (node (ref "R35") (pin "PAD_1") (pinfunction "PIN1_PAD_1") (pintype "passive"))
    )
    (net (code "132") (name "Net-(LI3-D)") (class "Default")
      (node (ref "LI3") (pin "2") (pinfunction "D_2") (pintype "passive"))
      (node (ref "R32") (pin "PAD_1") (pinfunction "PIN1_PAD_1") (pintype "passive"))
    )
    (net (code "133") (name "Net-(LI3-DOT)") (class "Default")
      (node (ref "LI3") (pin "5") (pinfunction "DOT_5") (pintype "passive"))
      (node (ref "R37") (pin "PAD_1") (pinfunction "PIN1_PAD_1") (pintype "passive"))
    )
    (net (code "134") (name "Net-(LI3-E)") (class "Default")
      (node (ref "LI3") (pin "1") (pinfunction "E_1") (pintype "passive"))
      (node (ref "R30") (pin "PAD_1") (pinfunction "PIN1_PAD_1") (pintype "passive"))
    )
    (net (code "135") (name "Net-(LI3-F)") (class "Default")
      (node (ref "LI3") (pin "9") (pinfunction "F_9") (pintype "passive"))
      (node (ref "R33") (pin "PAD_1") (pinfunction "PIN1_PAD_1") (pintype "passive"))
    )
    (net (code "136") (name "Net-(LI3-G)") (class "Default")
      (node (ref "LI3") (pin "10") (pinfunction "G_10") (pintype "passive"))
      (node (ref "R31") (pin "PAD_1") (pinfunction "PIN1_PAD_1") (pintype "passive"))
    )
    (net (code "137") (name "Net-(LI4-A)") (class "Default")
      (node (ref "LI4") (pin "7") (pinfunction "A_7") (pintype "passive"))
      (node (ref "R42") (pin "PAD_1") (pinfunction "PIN1_PAD_1") (pintype "passive"))
    )
    (net (code "138") (name "Net-(LI4-B)") (class "Default")
      (node (ref "LI4") (pin "6") (pinfunction "B_6") (pintype "passive"))
      (node (ref "R44") (pin "PAD_1") (pinfunction "PIN1_PAD_1") (pintype "passive"))
    )
    (net (code "139") (name "Net-(LI4-C)") (class "Default")
      (node (ref "LI4") (pin "4") (pinfunction "C_4") (pintype "passive"))
      (node (ref "R43") (pin "PAD_1") (pinfunction "PIN1_PAD_1") (pintype "passive"))
    )
    (net (code "140") (name "Net-(LI4-D)") (class "Default")
      (node (ref "LI4") (pin "2") (pinfunction "D_2") (pintype "passive"))
      (node (ref "R40") (pin "PAD_1") (pinfunction "PIN1_PAD_1") (pintype "passive"))
    )
    (net (code "141") (name "Net-(LI4-DOT)") (class "Default")
      (node (ref "LI4") (pin "5") (pinfunction "DOT_5") (pintype "passive"))
      (node (ref "R45") (pin "PAD_1") (pinfunction "PIN1_PAD_1") (pintype "passive"))
    )
    (net (code "142") (name "Net-(LI4-E)") (class "Default")
      (node (ref "LI4") (pin "1") (pinfunction "E_1") (pintype "passive"))
      (node (ref "R38") (pin "PAD_1") (pinfunction "PIN1_PAD_1") (pintype "passive"))
    )
    (net (code "143") (name "Net-(LI4-F)") (class "Default")
      (node (ref "LI4") (pin "9") (pinfunction "F_9") (pintype "passive"))
      (node (ref "R41") (pin "PAD_1") (pinfunction "PIN1_PAD_1") (pintype "passive"))
    )
    (net (code "144") (name "Net-(LI4-G)") (class "Default")
      (node (ref "LI4") (pin "10") (pinfunction "G_10") (pintype "passive"))
      (node (ref "R39") (pin "PAD_1") (pinfunction "PIN1_PAD_1") (pintype "passive"))
    )
    (net (code "145") (name "Net-(LI5-A)") (class "Default")
      (node (ref "LI5") (pin "7") (pinfunction "A_7") (pintype "passive"))
      (node (ref "R50") (pin "PAD_1") (pinfunction "PIN1_PAD_1") (pintype "passive"))
    )
    (net (code "146") (name "Net-(LI5-B)") (class "Default")
      (node (ref "LI5") (pin "6") (pinfunction "B_6") (pintype "passive"))
      (node (ref "R52") (pin "PAD_1") (pinfunction "PIN1_PAD_1") (pintype "passive"))
    )
    (net (code "147") (name "Net-(LI5-C)") (class "Default")
      (node (ref "LI5") (pin "4") (pinfunction "C_4") (pintype "passive"))
      (node (ref "R51") (pin "PAD_1") (pinfunction "PIN1_PAD_1") (pintype "passive"))
    )
    (net (code "148") (name "Net-(LI5-D)") (class "Default")
      (node (ref "LI5") (pin "2") (pinfunction "D_2") (pintype "passive"))
      (node (ref "R48") (pin "PAD_1") (pinfunction "PIN1_PAD_1") (pintype "passive"))
    )
    (net (code "149") (name "Net-(LI5-DOT)") (class "Default")
      (node (ref "LI5") (pin "5") (pinfunction "DOT_5") (pintype "passive"))
      (node (ref "R53") (pin "PAD_1") (pinfunction "PIN1_PAD_1") (pintype "passive"))
    )
    (net (code "150") (name "Net-(LI5-E)") (class "Default")
      (node (ref "LI5") (pin "1") (pinfunction "E_1") (pintype "passive"))
      (node (ref "R46") (pin "PAD_1") (pinfunction "PIN1_PAD_1") (pintype "passive"))
    )
    (net (code "151") (name "Net-(LI5-F)") (class "Default")
      (node (ref "LI5") (pin "9") (pinfunction "F_9") (pintype "passive"))
      (node (ref "R49") (pin "PAD_1") (pinfunction "PIN1_PAD_1") (pintype "passive"))
    )
    (net (code "152") (name "Net-(LI5-G)") (class "Default")
      (node (ref "LI5") (pin "10") (pinfunction "G_10") (pintype "passive"))
      (node (ref "R47") (pin "PAD_1") (pinfunction "PIN1_PAD_1") (pintype "passive"))
    )
    (net (code "153") (name "Net-(R2-PIN0)") (class "Default")
      (node (ref "KEY1") (pin "1") (pinfunction "1_1") (pintype "bidirectional"))
      (node (ref "KEY1") (pin "2") (pinfunction "1_2") (pintype "bidirectional"))
      (node (ref "R2") (pin "PAD_0") (pinfunction "PIN0_PAD_0") (pintype "passive"))
      (node (ref "R5") (pin "PAD_0") (pinfunction "PIN0_PAD_0") (pintype "passive"))
    )
    (net (code "154") (name "Net-(R3-PIN0)") (class "Default")
      (node (ref "KEY2") (pin "1") (pinfunction "1_1") (pintype "bidirectional"))
      (node (ref "KEY2") (pin "2") (pinfunction "1_2") (pintype "bidirectional"))
      (node (ref "R3") (pin "PAD_0") (pinfunction "PIN0_PAD_0") (pintype "passive"))
      (node (ref "R6") (pin "PAD_0") (pinfunction "PIN0_PAD_0") (pintype "passive"))
    )
    (net (code "155") (name "Net-(R4-PIN0)") (class "Default")
      (node (ref "KEY3") (pin "1") (pinfunction "1_1") (pintype "bidirectional"))
      (node (ref "KEY3") (pin "2") (pinfunction "1_2") (pintype "bidirectional"))
      (node (ref "R4") (pin "PAD_0") (pinfunction "PIN0_PAD_0") (pintype "passive"))
      (node (ref "R7") (pin "PAD_0") (pinfunction "PIN0_PAD_0") (pintype "passive"))
    )
    (net (code "156") (name "Net-(R56-PIN0)") (class "Default")
      (node (ref "R56") (pin "PAD_0") (pinfunction "PIN0_PAD_0") (pintype "passive"))
      (node (ref "T1") (pin "2") (pinfunction "E_2") (pintype "bidirectional"))
      (node (ref "T2") (pin "2") (pinfunction "E_2") (pintype "bidirectional"))
    )
    (net (code "157") (name "Net-(R56-PIN1)") (class "Default")
      (node (ref "D8") (pin "CATHODE") (pinfunction "CATHODE_CATHODE") (pintype "passive"))
      (node (ref "R56") (pin "PAD_1") (pinfunction "PIN1_PAD_1") (pintype "passive"))
      (node (ref "X2") (pin "1") (pinfunction "KL_1") (pintype "passive"))
    )
    (net (code "158") (name "Net-(R57-PIN0)") (class "Default")
      (node (ref "D8") (pin "ANODE") (pinfunction "ANODE_ANODE") (pintype "passive"))
      (node (ref "R57") (pin "PAD_0") (pinfunction "PIN0_PAD_0") (pintype "passive"))
    )
    (net (code "159") (name "Net-(R73-PIN0)") (class "Default")
      (node (ref "R73") (pin "PAD_0") (pinfunction "PIN0_PAD_0") (pintype "passive"))
      (node (ref "T3") (pin "2") (pinfunction "E_2") (pintype "bidirectional"))
      (node (ref "T7") (pin "2") (pinfunction "E_2") (pintype "bidirectional"))
    )
    (net (code "160") (name "Net-(R76-PIN1)") (class "Default")
      (node (ref "R76") (pin "PAD_1") (pinfunction "PIN1_PAD_1") (pintype "passive"))
      (node (ref "T4") (pin "2") (pinfunction "E_2") (pintype "bidirectional"))
    )
    (net (code "161") (name "Net-(R78-PIN1)") (class "Default")
      (node (ref "R78") (pin "PAD_1") (pinfunction "PIN1_PAD_1") (pintype "passive"))
      (node (ref "T5") (pin "2") (pinfunction "E_2") (pintype "bidirectional"))
    )
    (net (code "162") (name "Net-(R80-PIN1)") (class "Default")
      (node (ref "R80") (pin "PAD_1") (pinfunction "PIN1_PAD_1") (pintype "passive"))
      (node (ref "T6") (pin "2") (pinfunction "E_2") (pintype "bidirectional"))
    )
    (net (code "163") (name "Net-(TR1-SEC1_START)") (class "Default")
      (node (ref "D29") (pin "ANODE") (pinfunction "ANODE_ANODE") (pintype "passive"))
      (node (ref "TR1") (pin "W2_START") (pinfunction "SEC1_START_W2_START") (pintype "bidirectional"))
    )
    (net (code "164") (name "Net-(TR1-SEC2_START)") (class "Default")
      (node (ref "D28") (pin "ANODE") (pinfunction "ANODE_ANODE") (pintype "passive"))
      (node (ref "TR1") (pin "W3_START") (pinfunction "SEC2_START_W3_START") (pintype "bidirectional"))
    )
    (net (code "165") (name "USB_D+") (class "Default")
      (node (ref "R10") (pin "PAD_1") (pinfunction "PIN1_PAD_1") (pintype "passive"))
      (node (ref "X4") (pin "3") (pinfunction "D+_3") (pintype "bidirectional"))
      (node (ref "X5") (pin "3") (pinfunction "D+_3") (pintype "bidirectional"))
      (node (ref "ZD2") (pin "CATHODE") (pinfunction "CATHODE_CATHODE") (pintype "passive"))
    )
    (net (code "166") (name "USB_D-") (class "Default")
      (node (ref "J11") (pin "PAD_1") (pinfunction "PIN1_PAD_1") (pintype "passive"))
      (node (ref "R8") (pin "PAD_0") (pinfunction "PIN0_PAD_0") (pintype "passive"))
      (node (ref "R9") (pin "PAD_0") (pinfunction "PIN0_PAD_0") (pintype "passive"))
      (node (ref "X5") (pin "2") (pinfunction "D-_2") (pintype "bidirectional"))
      (node (ref "ZD1") (pin "CATHODE") (pinfunction "CATHODE_CATHODE") (pintype "passive"))
    )
    (net (code "167") (name "VCC_ROUGH") (class "Default")
      (node (ref "C10") (pin "PAD_1") (pinfunction "PIN1_PAD_1") (pintype "bidirectional"))
      (node (ref "C11") (pin "PAD_1") (pinfunction "PIN1_PAD_1") (pintype "bidirectional"))
      (node (ref "C12") (pin "PAD_1") (pinfunction "PIN1_PAD_1") (pintype "bidirectional"))
      (node (ref "C13") (pin "PAD_1") (pinfunction "PIN1_PAD_1") (pintype "bidirectional"))
      (node (ref "C14") (pin "PAD_1") (pinfunction "PIN1_PAD_1") (pintype "bidirectional"))
      (node (ref "C56") (pin "PAD_1") (pinfunction "PIN1_PAD_1") (pintype "bidirectional"))
      (node (ref "C57") (pin "+") (pinfunction "+_+") (pintype "bidirectional"))
      (node (ref "D1") (pin "CATHODE") (pinfunction "CATHODE_CATHODE") (pintype "passive"))
      (node (ref "D2") (pin "CATHODE") (pinfunction "CATHODE_CATHODE") (pintype "passive"))
      (node (ref "D29") (pin "CATHODE") (pinfunction "CATHODE_CATHODE") (pintype "passive"))
      (node (ref "D3") (pin "CATHODE") (pinfunction "CATHODE_CATHODE") (pintype "passive"))
      (node (ref "IC2") (pin "10") (pinfunction "~{SER_RES}_10") (pintype "bidirectional"))
      (node (ref "IC2") (pin "16") (pinfunction "VCC_16") (pintype "bidirectional"))
      (node (ref "IC3") (pin "10") (pinfunction "~{SER_RES}_10") (pintype "bidirectional"))
      (node (ref "IC3") (pin "16") (pinfunction "VCC_16") (pintype "bidirectional"))
      (node (ref "IC4") (pin "10") (pinfunction "~{SER_RES}_10") (pintype "bidirectional"))
      (node (ref "IC4") (pin "16") (pinfunction "VCC_16") (pintype "bidirectional"))
      (node (ref "IC5") (pin "10") (pinfunction "~{SER_RES}_10") (pintype "bidirectional"))
      (node (ref "IC5") (pin "16") (pinfunction "VCC_16") (pintype "bidirectional"))
      (node (ref "IC6") (pin "10") (pinfunction "~{SER_RES}_10") (pintype "bidirectional"))
      (node (ref "IC6") (pin "16") (pinfunction "VCC_16") (pintype "bidirectional"))
      (node (ref "R84") (pin "PAD1") (pinfunction "PIN1_PAD1") (pintype "passive"))
    )
    (net (code "168") (name "unconnected-(IC1-(ADC1)PA1-Pad36)") (class "Default")
      (node (ref "IC1") (pin "36") (pinfunction "(ADC1)PA1_36") (pintype "bidirectional"))
    )
    (net (code "169") (name "unconnected-(IC1-(ADC6)PA6-Pad31)") (class "Default")
      (node (ref "IC1") (pin "31") (pinfunction "(ADC6)PA6_31") (pintype "bidirectional"))
    )
    (net (code "170") (name "unconnected-(IC1-(ADC7)PA7-Pad30)") (class "Default")
      (node (ref "IC1") (pin "30") (pinfunction "(ADC7)PA7_30") (pintype "bidirectional"))
    )
    (net (code "171") (name "unconnected-(IC1-(AIN0{slash}INT2)PB2-Pad42)") (class "Default")
      (node (ref "IC1") (pin "42") (pinfunction "(AIN0/INT2)PB2_42") (pintype "bidirectional"))
    )
    (net (code "172") (name "unconnected-(IC1-(AIN1{slash}OC0)PB3-Pad43)") (class "Default")
      (node (ref "IC1") (pin "43") (pinfunction "(AIN1/OC0)PB3_43") (pintype "bidirectional"))
    )
    (net (code "173") (name "unconnected-(IC1-(ICP)PD6-Pad15)") (class "Default")
      (node (ref "IC1") (pin "15") (pinfunction "(ICP)PD6_15") (pintype "bidirectional"))
    )
    (net (code "174") (name "unconnected-(IC1-(OC2)PD7-Pad16)") (class "Default")
      (node (ref "IC1") (pin "16") (pinfunction "(OC2)PD7_16") (pintype "bidirectional"))
    )
    (net (code "175") (name "unconnected-(IC1-(RXD)PD0-Pad9)") (class "Default")
      (node (ref "IC1") (pin "9") (pinfunction "(RXD)PD0_9") (pintype "bidirectional"))
    )
    (net (code "176") (name "unconnected-(IC1-(SS)PB4-Pad44)") (class "Default")
      (node (ref "IC1") (pin "44") (pinfunction "(SS)PB4_44") (pintype "bidirectional"))
    )
    (net (code "177") (name "unconnected-(IC1-(T0{slash}XCK)PB0-Pad40)") (class "Default")
      (node (ref "IC1") (pin "40") (pinfunction "(T0/XCK)PB0_40") (pintype "bidirectional"))
    )
    (net (code "178") (name "unconnected-(IC1-(T1)PB1-Pad41)") (class "Default")
      (node (ref "IC1") (pin "41") (pinfunction "(T1)PB1_41") (pintype "bidirectional"))
    )
    (net (code "179") (name "unconnected-(IC1-(TOSC2)PC7-Pad26)") (class "Default")
      (node (ref "IC1") (pin "26") (pinfunction "(TOSC2)PC7_26") (pintype "bidirectional"))
    )
    (net (code "180") (name "unconnected-(IC1-PC0(SCL)-Pad19)") (class "Default")
      (node (ref "IC1") (pin "19") (pinfunction "PC0(SCL)_19") (pintype "bidirectional"))
    )
    (net (code "181") (name "unconnected-(IC6-SER_OUT-Pad9)") (class "Default")
      (node (ref "IC6") (pin "9") (pinfunction "SER_OUT_9") (pintype "bidirectional"))
    )
    (net (code "182") (name "unconnected-(X4-ID-Pad4)") (class "Default")
      (node (ref "X4") (pin "4") (pinfunction "ID_4") (pintype "bidirectional"))
    )
  )
)
